# mainboard_r15_eurobot2014_r1.net
KiCad netlist of a schematic drawn in EAGLE
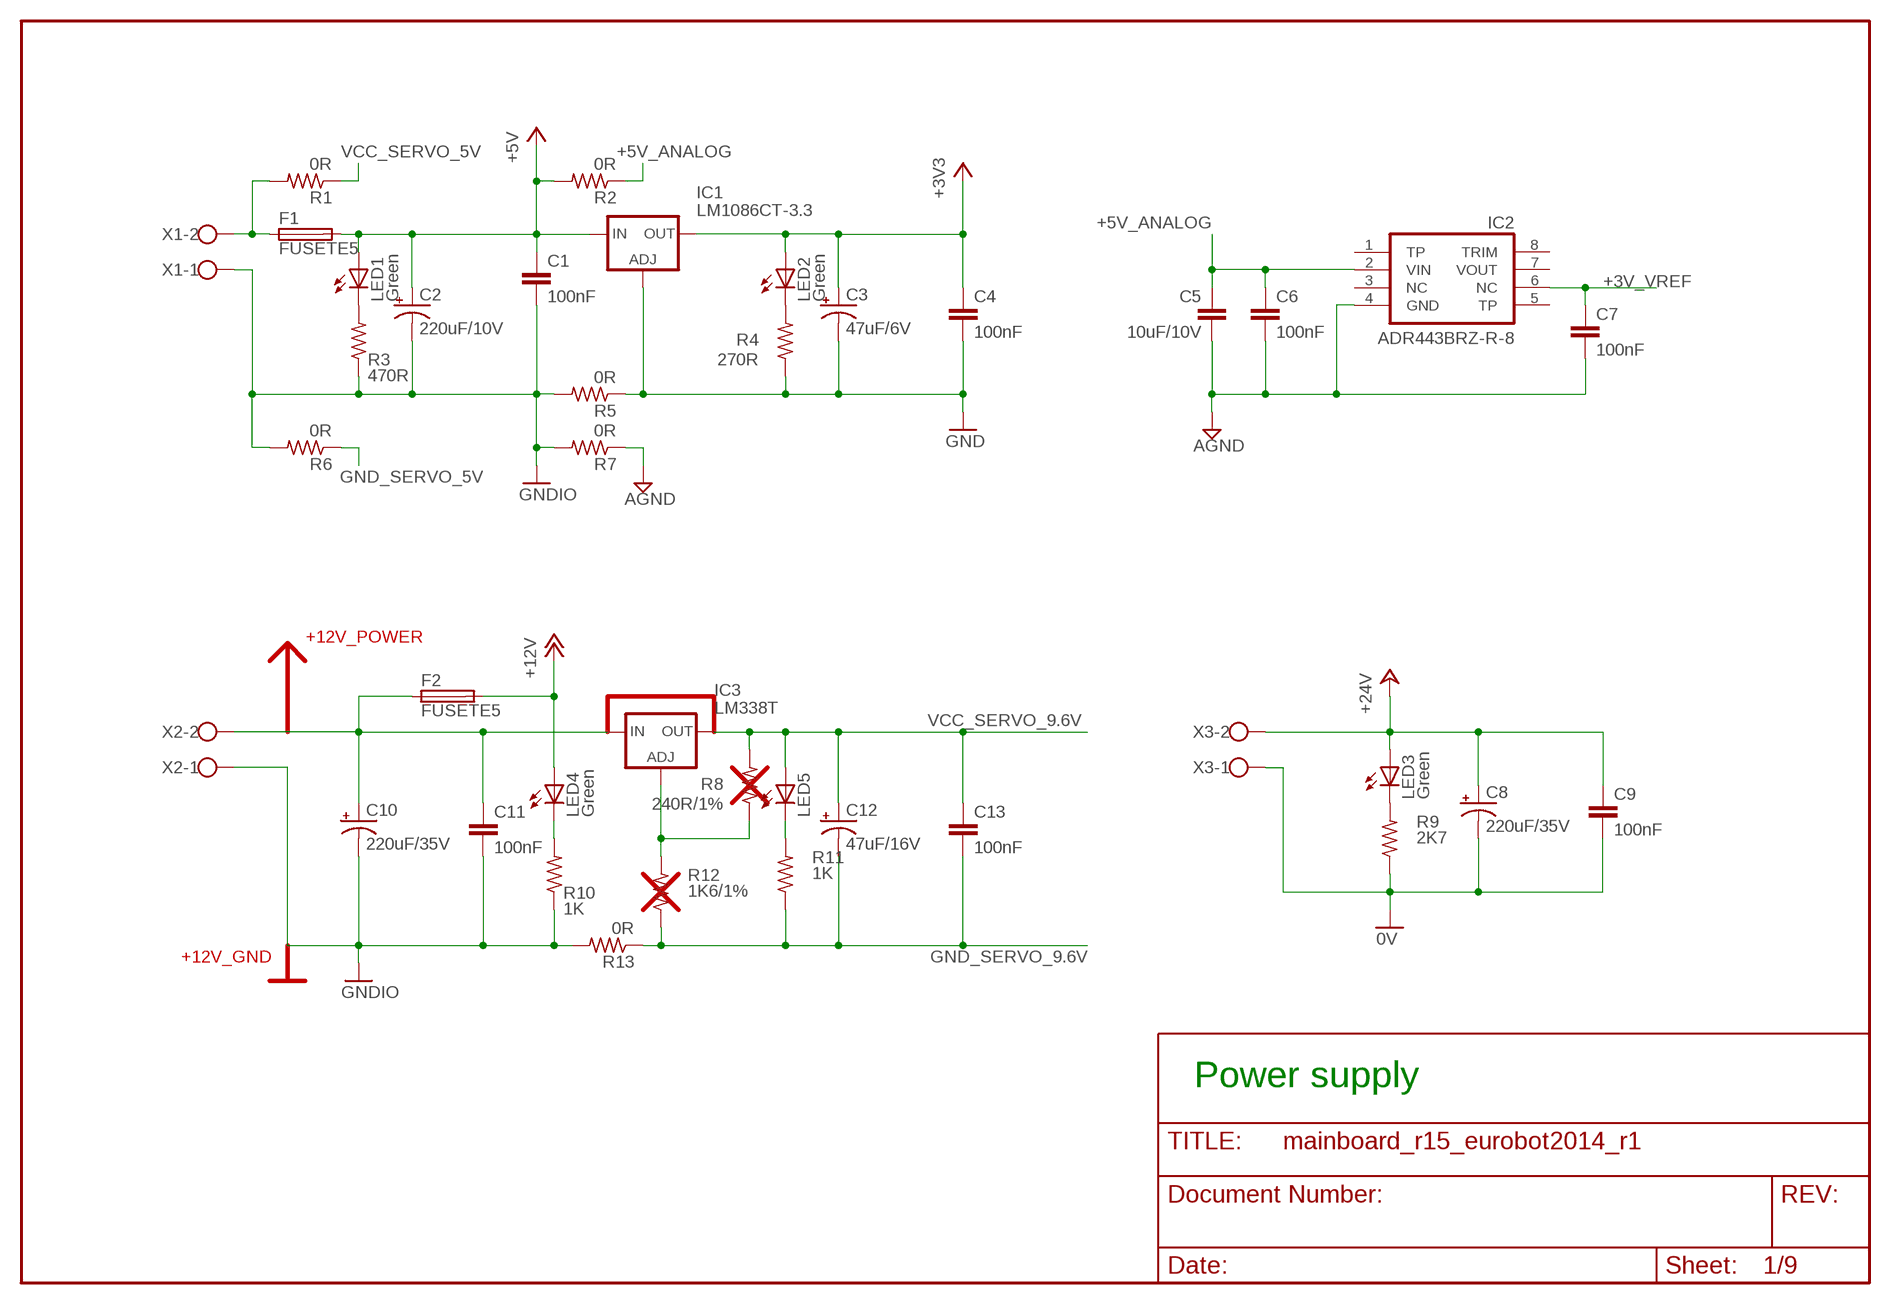
[diagram p0: schematic, sheet 1]
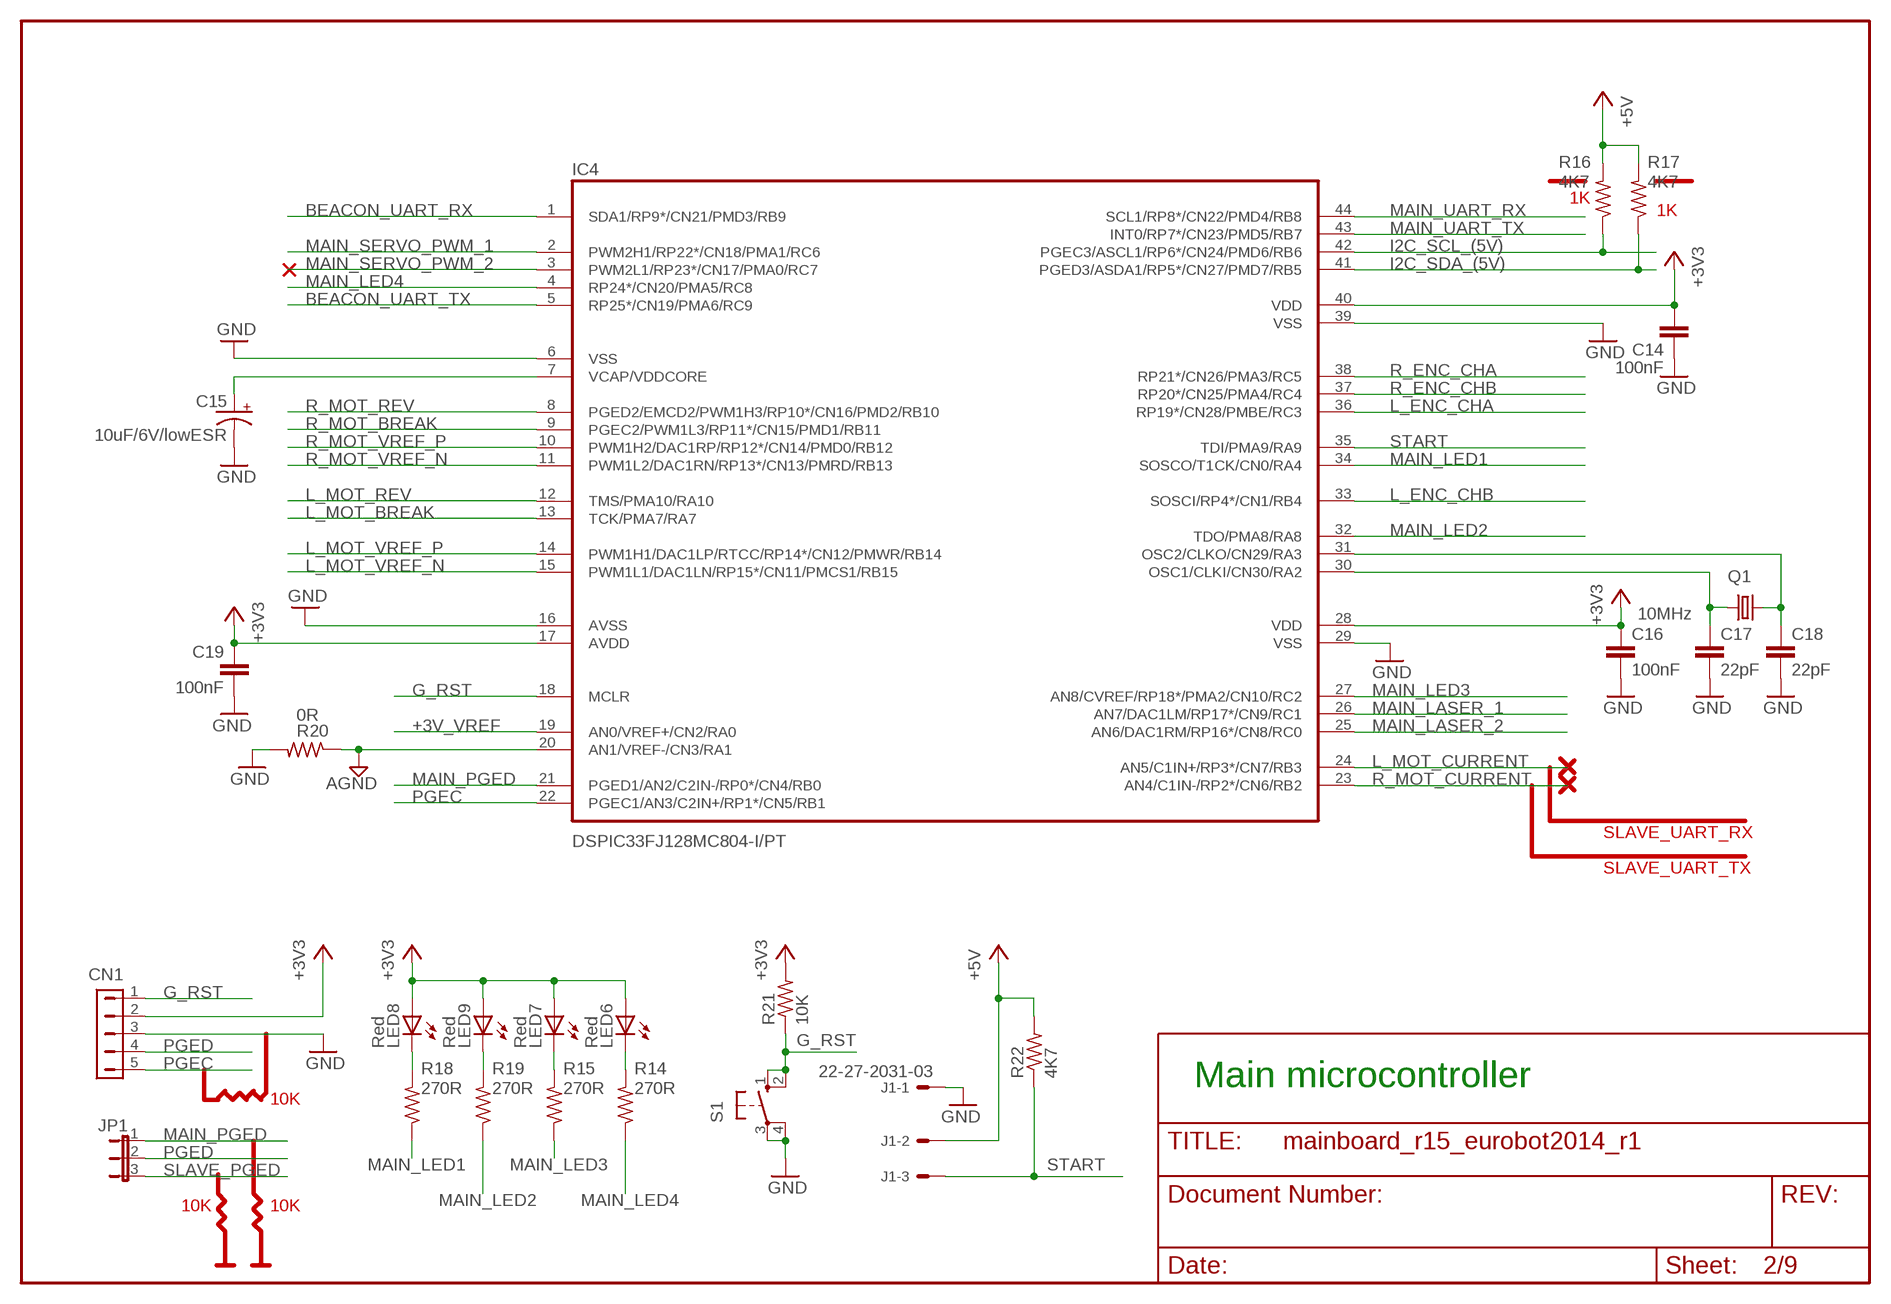
[diagram p1: schematic, sheet 2]
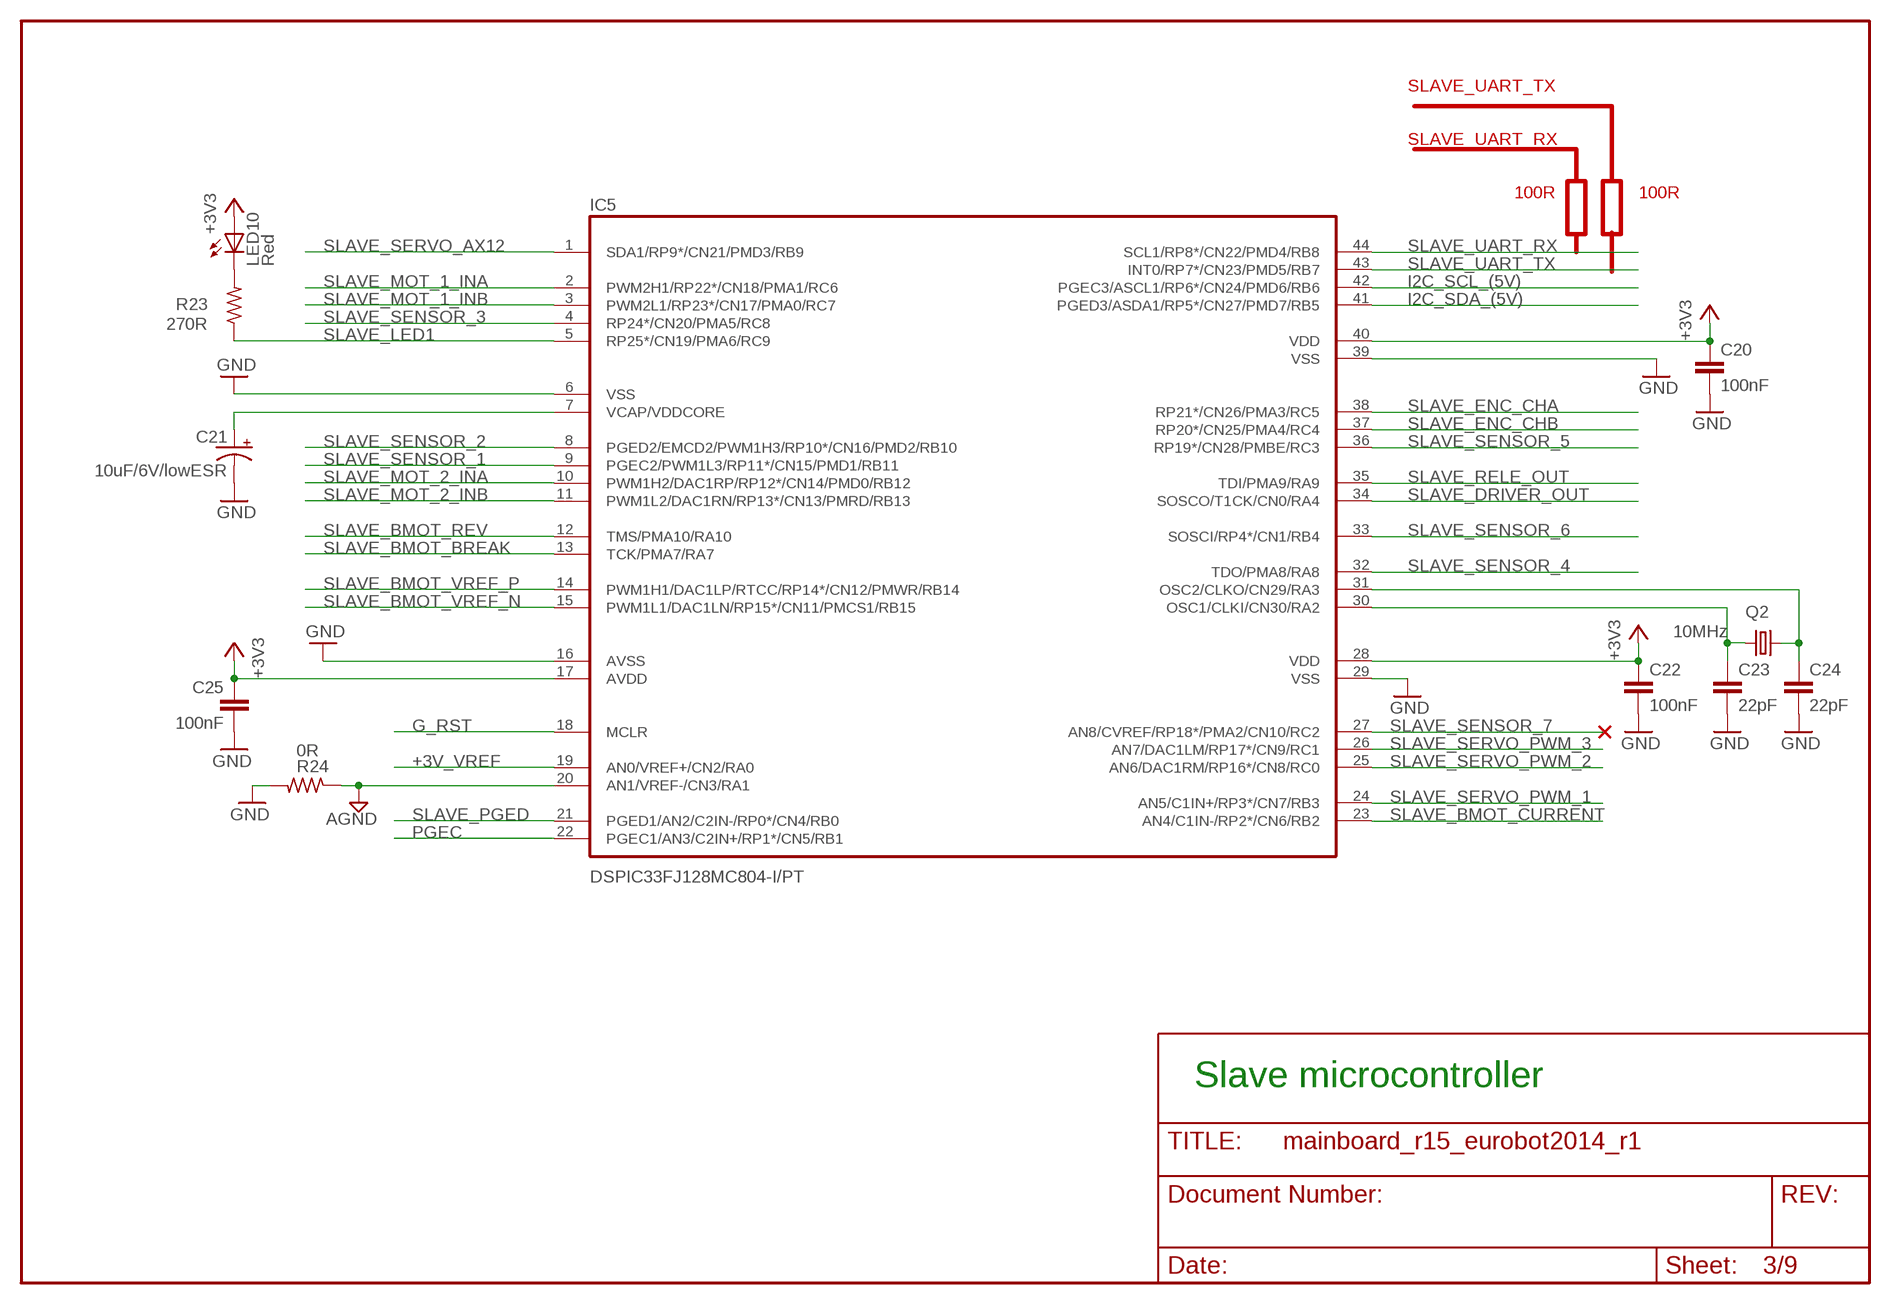
[diagram p2: schematic, sheet 3]
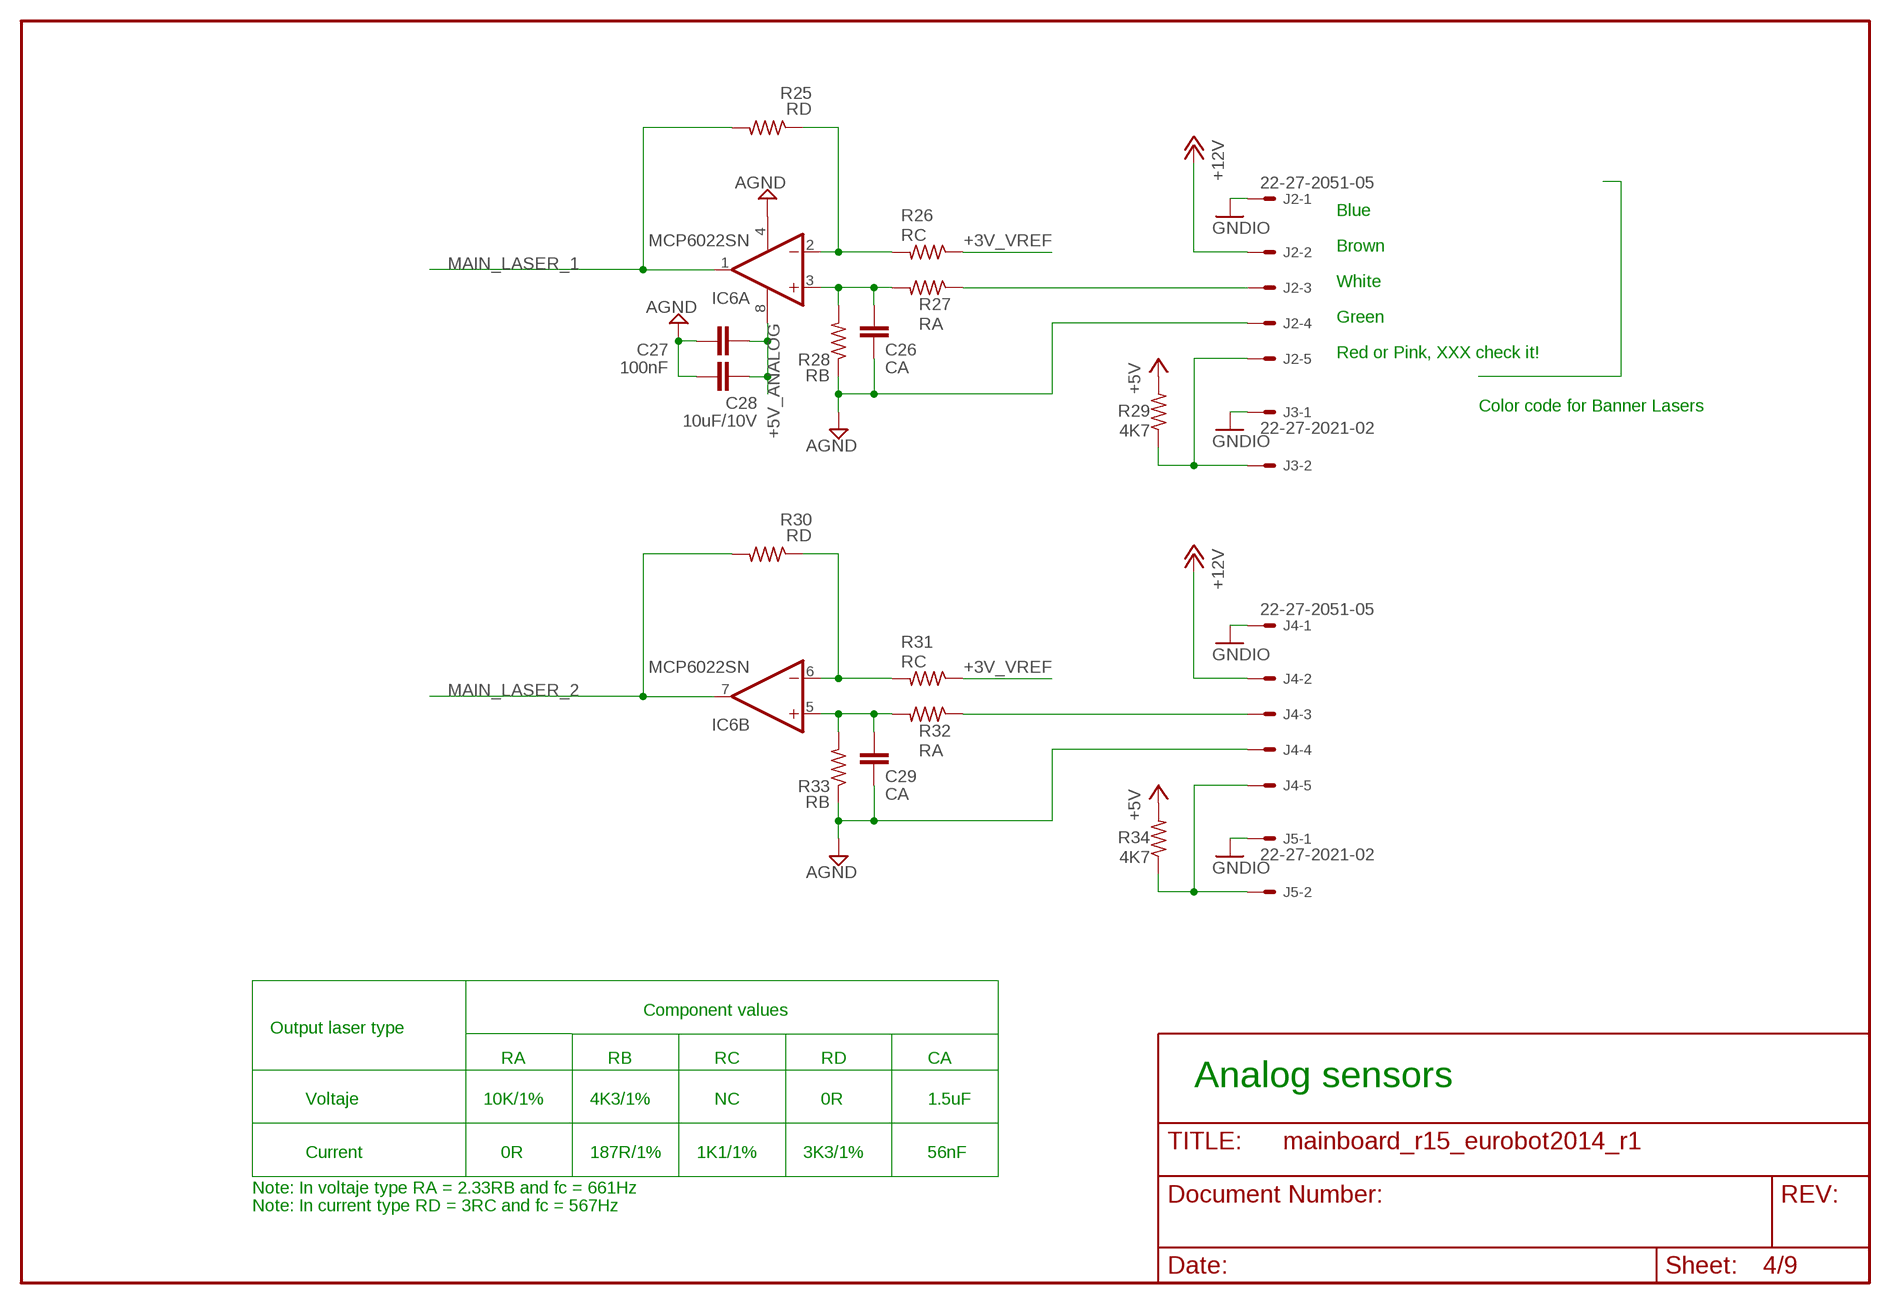
[diagram p3: schematic, sheet 4]
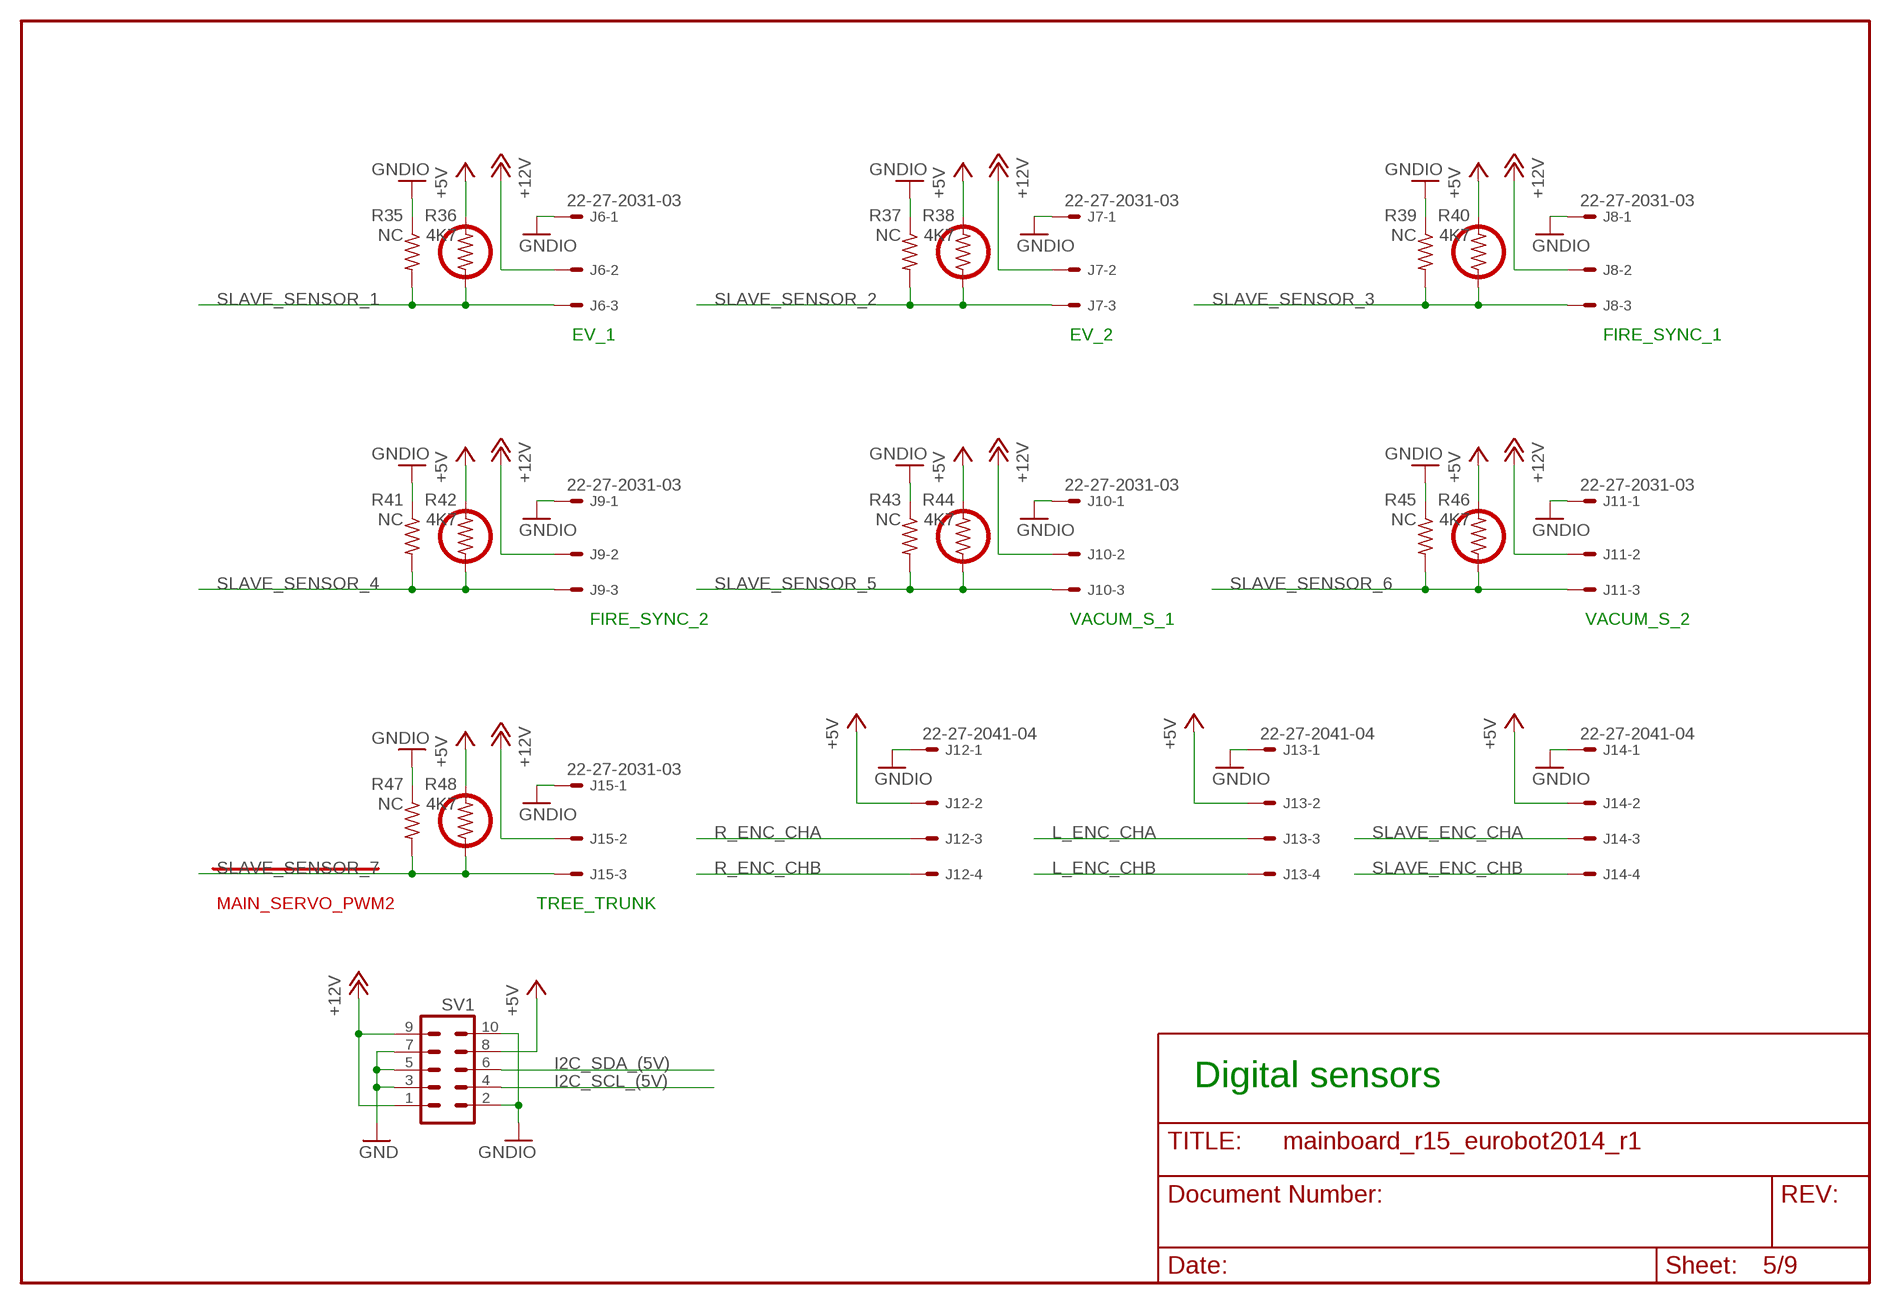
[diagram p4: schematic, sheet 5]
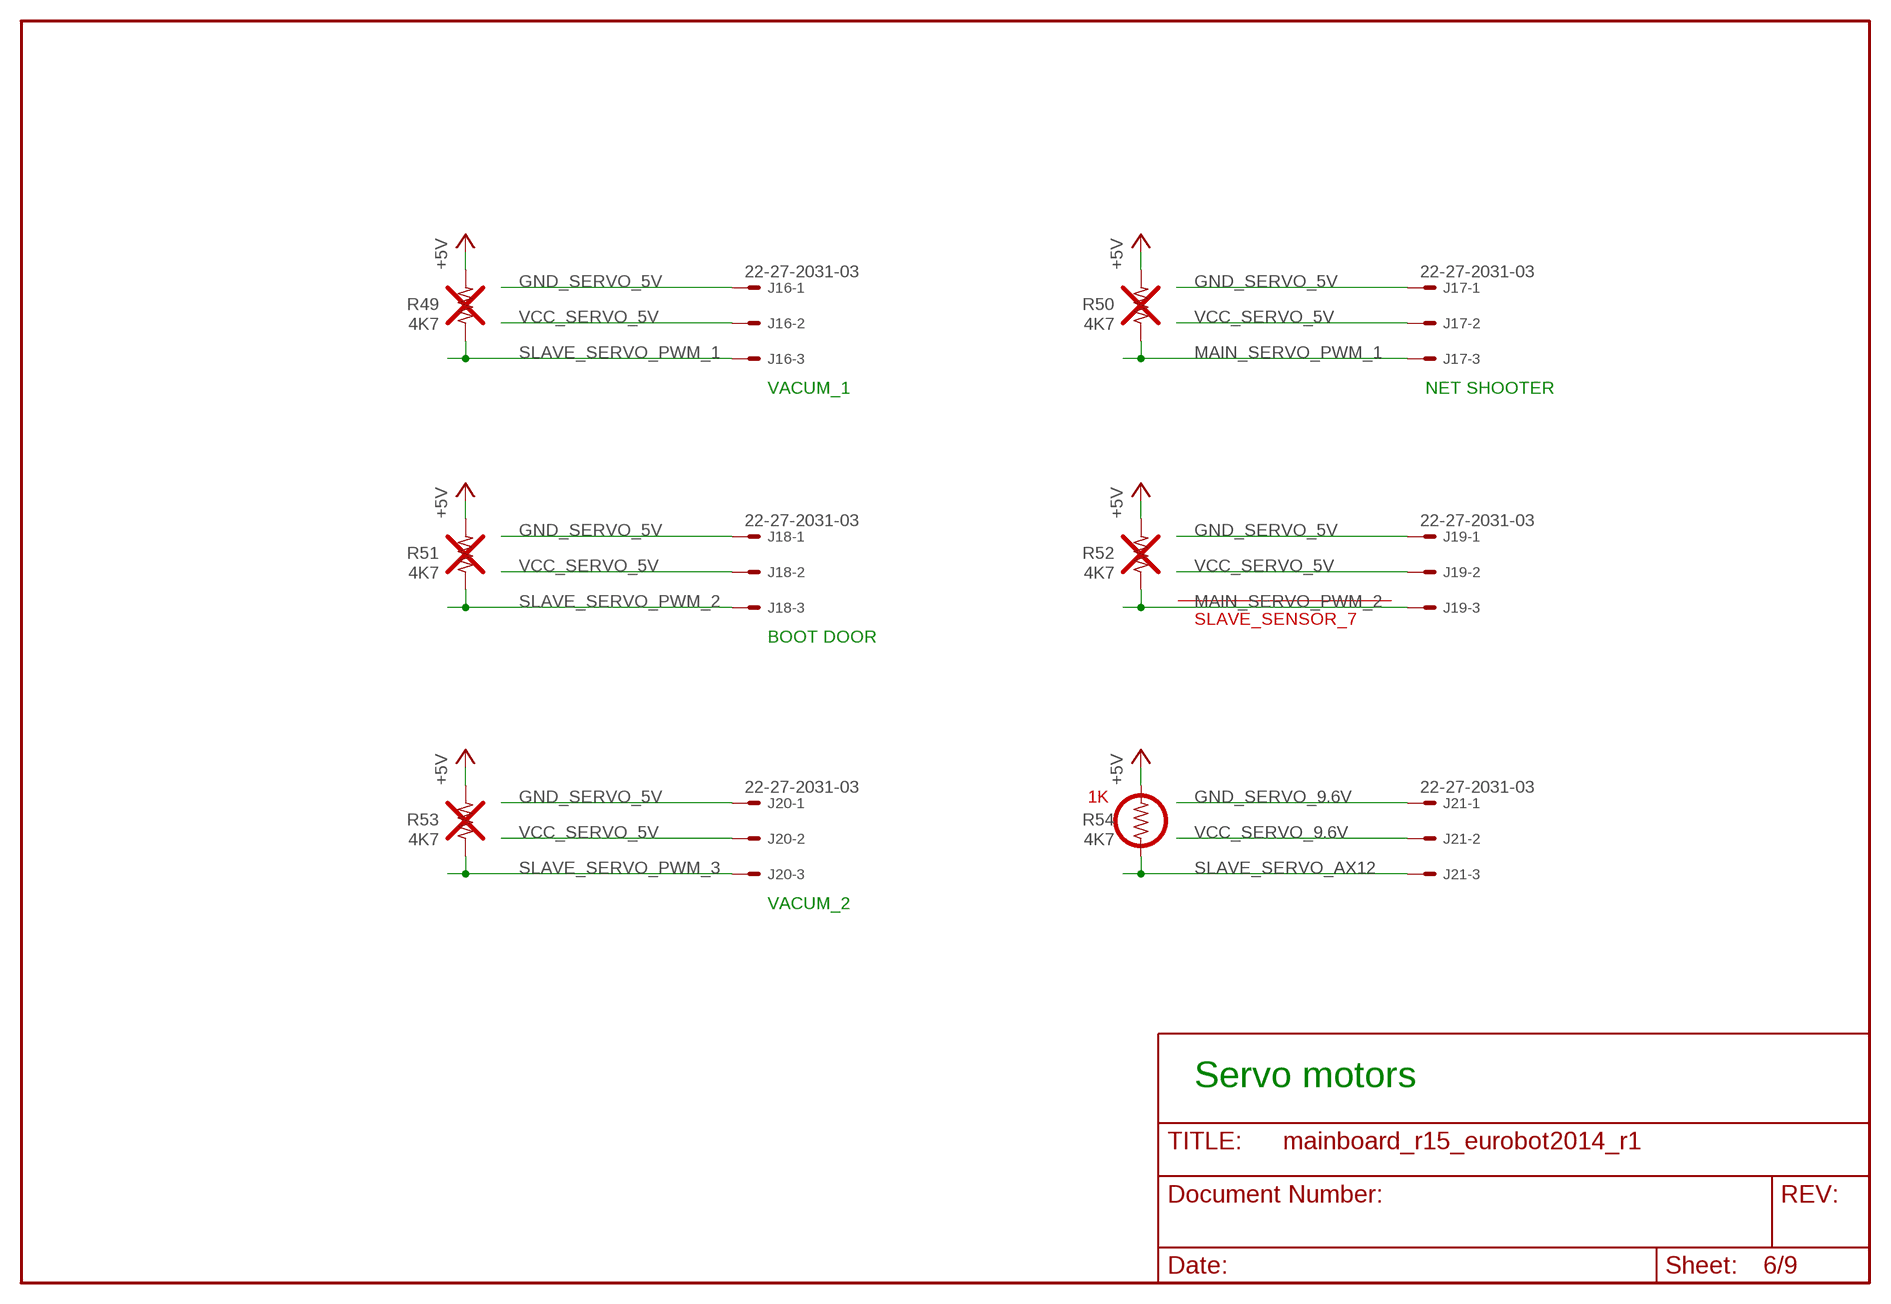
[diagram p5: schematic, sheet 6]
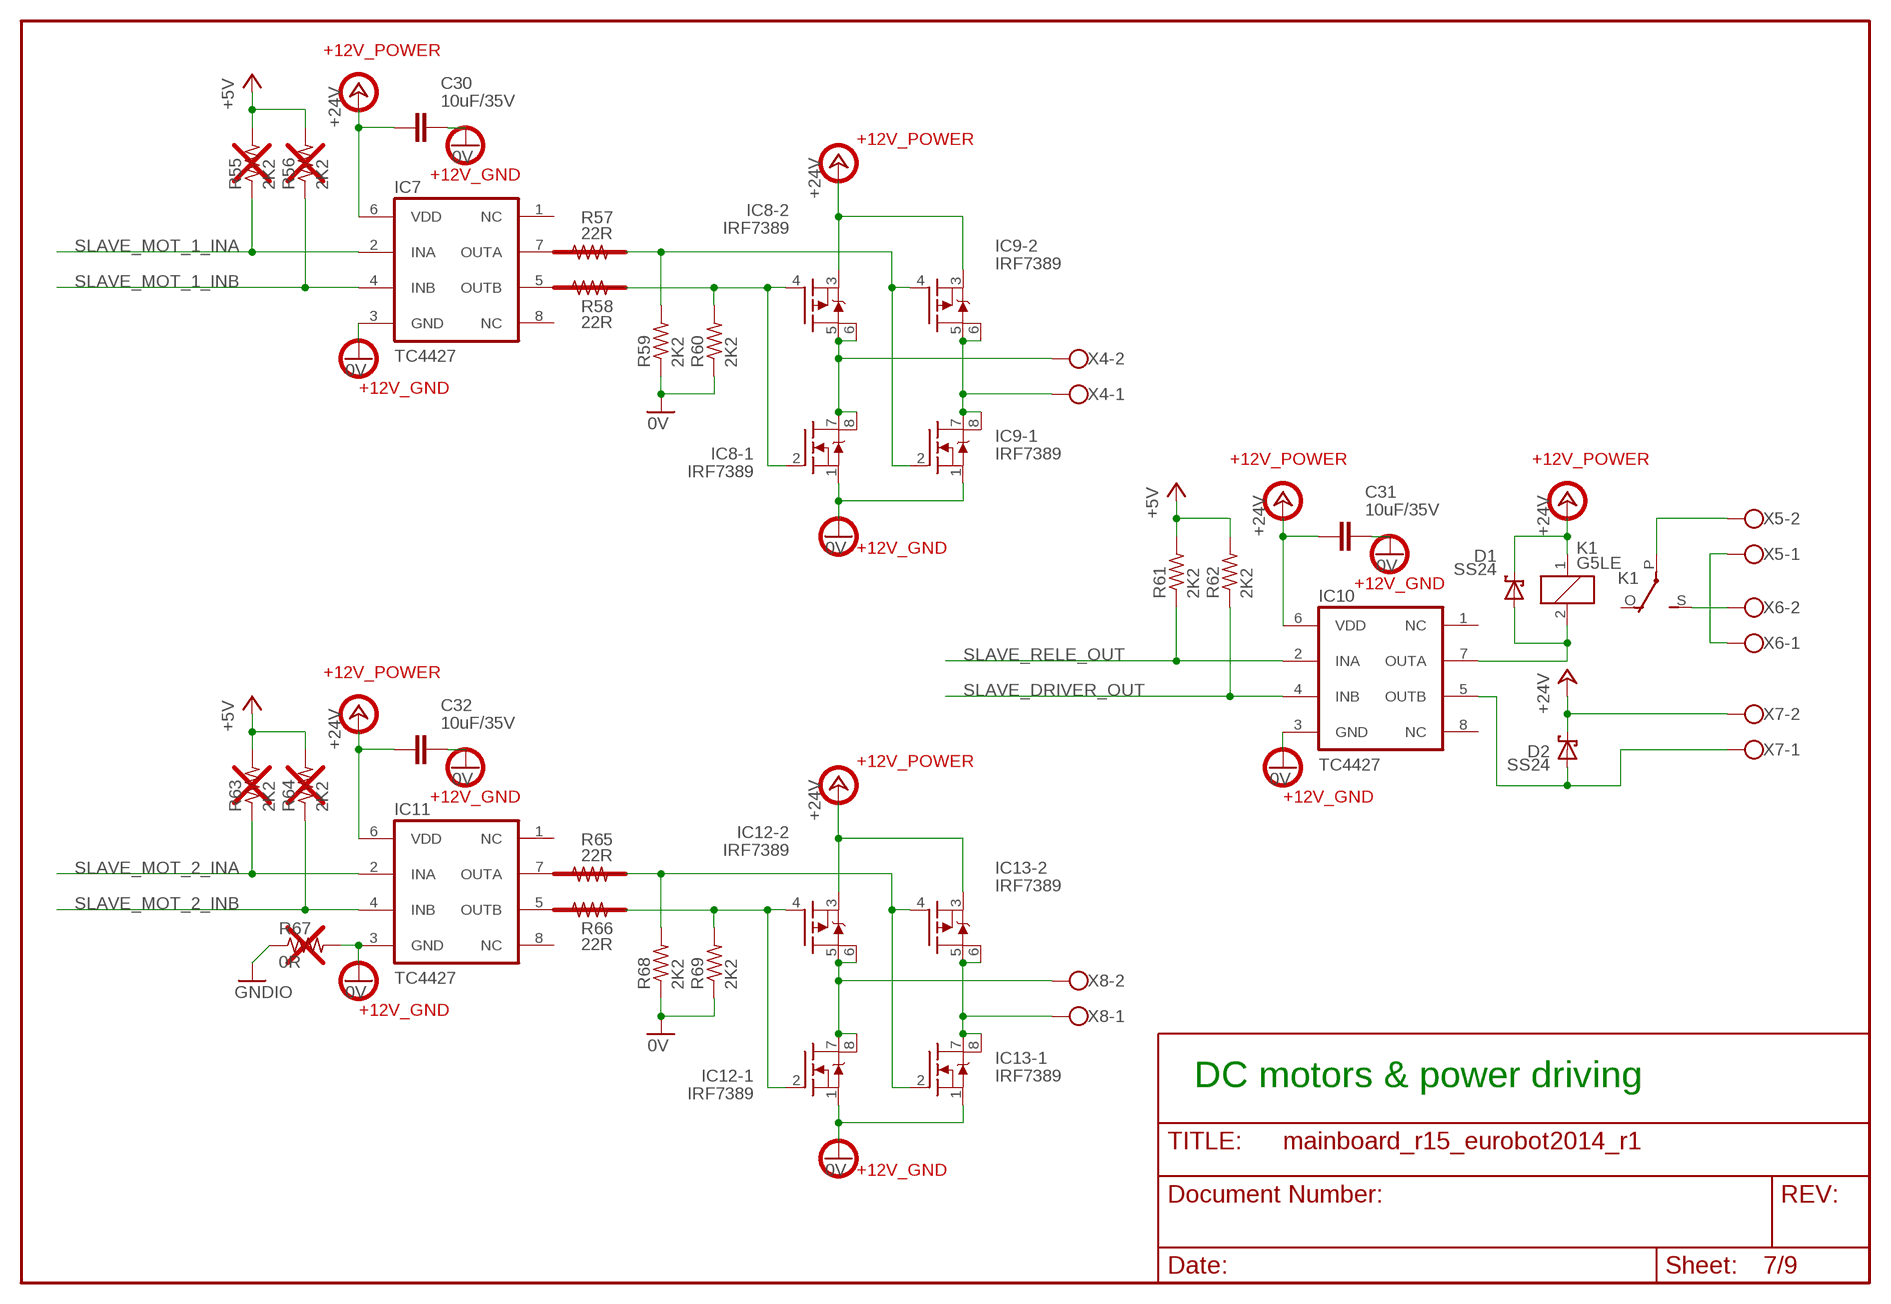
[diagram p6: schematic, sheet 7]
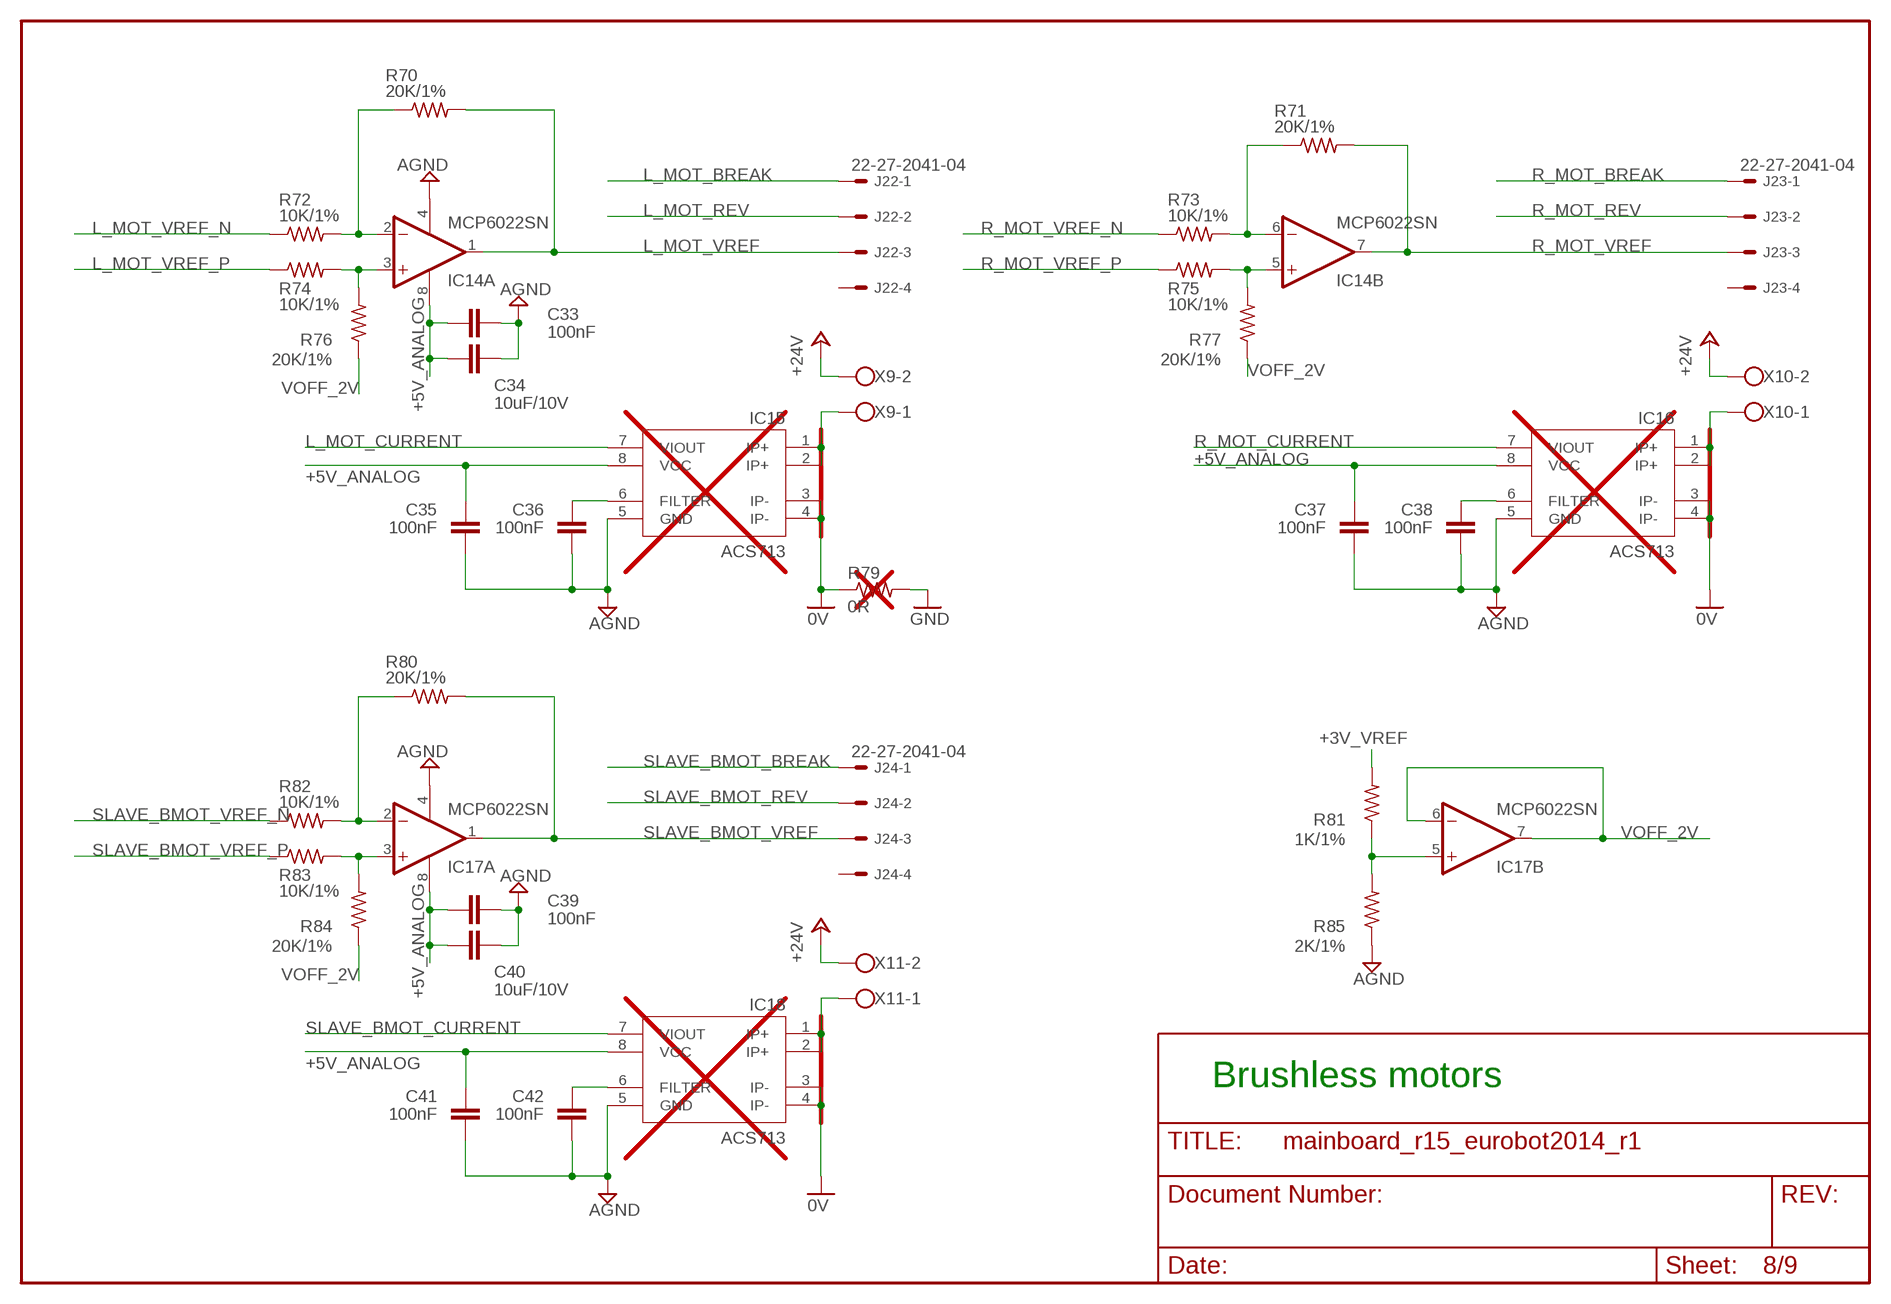
[diagram p7: schematic, sheet 8]
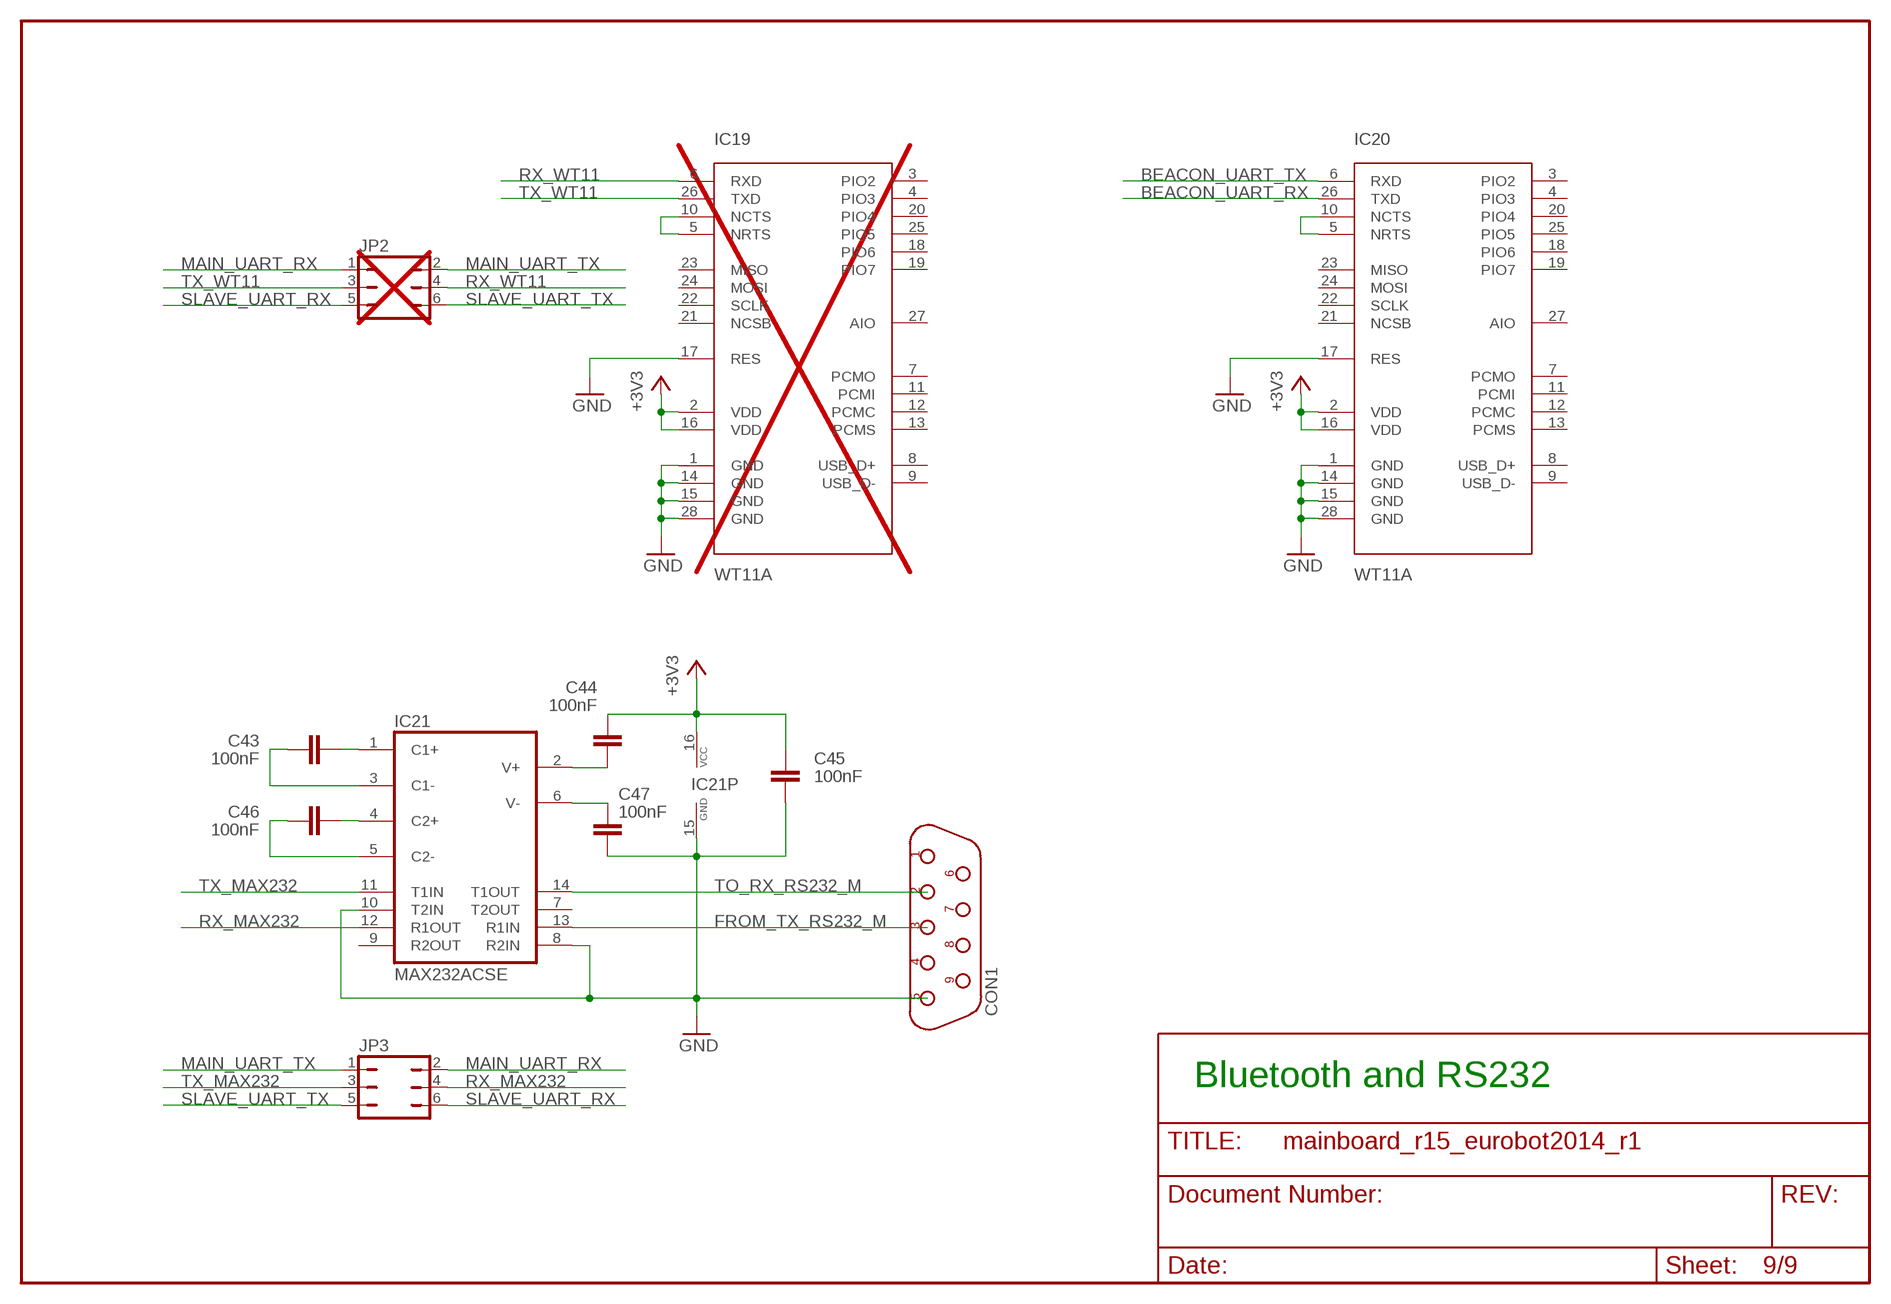
[diagram p8: schematic, sheet 9]

(export (version "E")
  (design (tool "Eeschema 10.0.6"))
  (components
    (comp (ref "C20")
      (value "100nF")
      (footprint "eagle-import:C0603")
      (libsource (lib "eagle-import") (part "C-EUC0603"))
    )
    (comp (ref "C21")
      (value "10uF/6V/lowESR")
      (footprint "eagle-import:SMC_A")
      (libsource (lib "eagle-import") (part "CPOL-USSMCA"))
    )
    (comp (ref "C22")
      (value "100nF")
      (footprint "eagle-import:C0603")
      (libsource (lib "eagle-import") (part "C-EUC0603"))
    )
    (comp (ref "C23")
      (value "22pF")
      (footprint "eagle-import:C0805")
      (libsource (lib "eagle-import") (part "C-EUC0805"))
    )
    (comp (ref "C24")
      (value "22pF")
      (footprint "eagle-import:C0805")
      (libsource (lib "eagle-import") (part "C-EUC0805"))
    )
    (comp (ref "C25")
      (value "100nF")
      (footprint "eagle-import:C0603")
      (libsource (lib "eagle-import") (part "C-EUC0603"))
    )
    (comp (ref "IC5")
      (value "DSPIC33FJ128MC804-I/PT")
      (footprint "eagle-import:TQFP44")
      (libsource (lib "eagle-import") (part "DSPIC33FJXXMC804SMD"))
    )
    (comp (ref "LED10")
      (value "Red")
      (footprint "eagle-import:CHIP-LED0805")
      (libsource (lib "eagle-import") (part "LEDCHIP-LED0805"))
    )
    (comp (ref "Q2")
      (value "10MHz")
      (footprint "eagle-import:HC49UP")
      (libsource (lib "eagle-import") (part "CRYSTALHC49UP"))
    )
    (comp (ref "R23")
      (value "270R")
      (footprint "eagle-import:R0805")
      (libsource (lib "eagle-import") (part "R-US_R0805"))
    )
    (comp (ref "R24")
      (value "0R")
      (footprint "eagle-import:R0805")
      (libsource (lib "eagle-import") (part "R-US_R0805"))
    )
    (comp (ref "C30")
      (value "10uF/35V")
      (footprint "eagle-import:C1206")
      (libsource (lib "eagle-import") (part "C-EUC1206"))
    )
    (comp (ref "C31")
      (value "10uF/35V")
      (footprint "eagle-import:C1206")
      (libsource (lib "eagle-import") (part "C-EUC1206"))
    )
    (comp (ref "C32")
      (value "10uF/35V")
      (footprint "eagle-import:C1206")
      (libsource (lib "eagle-import") (part "C-EUC1206"))
    )
    (comp (ref "D1")
      (value "SS24")
      (footprint "eagle-import:DIOM5436X265N")
      (libsource (lib "eagle-import") (part "SCHOTTKY_SMB"))
    )
    (comp (ref "D2")
      (value "SS24")
      (footprint "eagle-import:DIOM5436X265N")
      (libsource (lib "eagle-import") (part "SCHOTTKY_SMB"))
    )
    (comp (ref "IC7")
      (value "TC4427")
      (footprint "eagle-import:SO08")
      (libsource (lib "eagle-import") (part "TC4427OA"))
    )
    (comp (ref "IC8")
      (value "IRF7389")
      (footprint "eagle-import:SO08")
      (libsource (lib "eagle-import") (part "IRF7389"))
    )
    (comp (ref "IC9")
      (value "IRF7389")
      (footprint "eagle-import:SO08")
      (libsource (lib "eagle-import") (part "IRF7389"))
    )
    (comp (ref "IC10")
      (value "TC4427")
      (footprint "eagle-import:SO08")
      (libsource (lib "eagle-import") (part "TC4427OA"))
    )
    (comp (ref "IC11")
      (value "TC4427")
      (footprint "eagle-import:SO08")
      (libsource (lib "eagle-import") (part "TC4427OA"))
    )
    (comp (ref "IC12")
      (value "IRF7389")
      (footprint "eagle-import:SO08")
      (libsource (lib "eagle-import") (part "IRF7389"))
    )
    (comp (ref "IC13")
      (value "IRF7389")
      (footprint "eagle-import:SO08")
      (libsource (lib "eagle-import") (part "IRF7389"))
    )
    (comp (ref "K1")
      (value "G5LE")
      (footprint "eagle-import:G5LE")
      (libsource (lib "eagle-import") (part "G5LE"))
    )
    (comp (ref "R55")
      (value "2K2")
      (footprint "eagle-import:R0805")
      (libsource (lib "eagle-import") (part "R-US_R0805"))
    )
    (comp (ref "R56")
      (value "2K2")
      (footprint "eagle-import:R0805")
      (libsource (lib "eagle-import") (part "R-US_R0805"))
    )
    (comp (ref "R57")
      (value "22R")
      (footprint "eagle-import:R0805")
      (libsource (lib "eagle-import") (part "R-US_R0805"))
    )
    (comp (ref "R58")
      (value "22R")
      (footprint "eagle-import:R0805")
      (libsource (lib "eagle-import") (part "R-US_R0805"))
    )
    (comp (ref "R59")
      (value "2K2")
      (footprint "eagle-import:R0805")
      (libsource (lib "eagle-import") (part "R-US_R0805"))
    )
    (comp (ref "R60")
      (value "2K2")
      (footprint "eagle-import:R0805")
      (libsource (lib "eagle-import") (part "R-US_R0805"))
    )
    (comp (ref "R61")
      (value "2K2")
      (footprint "eagle-import:R0805")
      (libsource (lib "eagle-import") (part "R-US_R0805"))
    )
    (comp (ref "R62")
      (value "2K2")
      (footprint "eagle-import:R0805")
      (libsource (lib "eagle-import") (part "R-US_R0805"))
    )
    (comp (ref "R63")
      (value "2K2")
      (footprint "eagle-import:R0805")
      (libsource (lib "eagle-import") (part "R-US_R0805"))
    )
    (comp (ref "R64")
      (value "2K2")
      (footprint "eagle-import:R0805")
      (libsource (lib "eagle-import") (part "R-US_R0805"))
    )
    (comp (ref "R65")
      (value "22R")
      (footprint "eagle-import:R0805")
      (libsource (lib "eagle-import") (part "R-US_R0805"))
    )
    (comp (ref "R66")
      (value "22R")
      (footprint "eagle-import:R0805")
      (libsource (lib "eagle-import") (part "R-US_R0805"))
    )
    (comp (ref "R67")
      (value "0R")
      (footprint "eagle-import:R0805")
      (libsource (lib "eagle-import") (part "R-US_R0805"))
    )
    (comp (ref "R68")
      (value "2K2")
      (footprint "eagle-import:R0805")
      (libsource (lib "eagle-import") (part "R-US_R0805"))
    )
    (comp (ref "R69")
      (value "2K2")
      (footprint "eagle-import:R0805")
      (libsource (lib "eagle-import") (part "R-US_R0805"))
    )
    (comp (ref "X4")
      (value "W237-02P")
      (footprint "eagle-import:W237-132")
      (libsource (lib "eagle-import") (part "W237-02P"))
    )
    (comp (ref "X5")
      (value "W237-02P")
      (footprint "eagle-import:W237-132")
      (libsource (lib "eagle-import") (part "W237-02P"))
    )
    (comp (ref "X6")
      (value "W237-02P")
      (footprint "eagle-import:W237-132")
      (libsource (lib "eagle-import") (part "W237-02P"))
    )
    (comp (ref "X7")
      (value "W237-02P")
      (footprint "eagle-import:W237-132")
      (libsource (lib "eagle-import") (part "W237-02P"))
    )
    (comp (ref "X8")
      (value "W237-02P")
      (footprint "eagle-import:W237-132")
      (libsource (lib "eagle-import") (part "W237-02P"))
    )
    (comp (ref "J16")
      (value "22-27-2031-03")
      (footprint "eagle-import:6410-03")
      (libsource (lib "eagle-import") (part "22-?-0327-2031"))
    )
    (comp (ref "J17")
      (value "22-27-2031-03")
      (footprint "eagle-import:6410-03")
      (libsource (lib "eagle-import") (part "22-?-0327-2031"))
    )
    (comp (ref "J18")
      (value "22-27-2031-03")
      (footprint "eagle-import:6410-03")
      (libsource (lib "eagle-import") (part "22-?-0327-2031"))
    )
    (comp (ref "J19")
      (value "22-27-2031-03")
      (footprint "eagle-import:6410-03")
      (libsource (lib "eagle-import") (part "22-?-0327-2031"))
    )
    (comp (ref "J20")
      (value "22-27-2031-03")
      (footprint "eagle-import:6410-03")
      (libsource (lib "eagle-import") (part "22-?-0327-2031"))
    )
    (comp (ref "J21")
      (value "22-27-2031-03")
      (footprint "eagle-import:6410-03")
      (libsource (lib "eagle-import") (part "22-?-0327-2031"))
    )
    (comp (ref "R49")
      (value "4K7")
      (footprint "eagle-import:R0805")
      (libsource (lib "eagle-import") (part "R-US_R0805"))
    )
    (comp (ref "R50")
      (value "4K7")
      (footprint "eagle-import:R0805")
      (libsource (lib "eagle-import") (part "R-US_R0805"))
    )
    (comp (ref "R51")
      (value "4K7")
      (footprint "eagle-import:R0805")
      (libsource (lib "eagle-import") (part "R-US_R0805"))
    )
    (comp (ref "R52")
      (value "4K7")
      (footprint "eagle-import:R0805")
      (libsource (lib "eagle-import") (part "R-US_R0805"))
    )
    (comp (ref "R53")
      (value "4K7")
      (footprint "eagle-import:R0805")
      (libsource (lib "eagle-import") (part "R-US_R0805"))
    )
    (comp (ref "R54")
      (value "4K7")
      (footprint "eagle-import:R0805")
      (libsource (lib "eagle-import") (part "R-US_R0805"))
    )
    (comp (ref "C33")
      (value "100nF")
      (footprint "eagle-import:C0805")
      (libsource (lib "eagle-import") (part "C-EUC0805"))
    )
    (comp (ref "C34")
      (value "10uF/10V")
      (footprint "eagle-import:C1206")
      (libsource (lib "eagle-import") (part "C-EUC1206"))
    )
    (comp (ref "C35")
      (value "100nF")
      (footprint "eagle-import:C0805")
      (libsource (lib "eagle-import") (part "C-EUC0805"))
    )
    (comp (ref "C36")
      (value "100nF")
      (footprint "eagle-import:C0805")
      (libsource (lib "eagle-import") (part "C-EUC0805"))
    )
    (comp (ref "C37")
      (value "100nF")
      (footprint "eagle-import:C0805")
      (libsource (lib "eagle-import") (part "C-EUC0805"))
    )
    (comp (ref "C38")
      (value "100nF")
      (footprint "eagle-import:C0805")
      (libsource (lib "eagle-import") (part "C-EUC0805"))
    )
    (comp (ref "C39")
      (value "100nF")
      (footprint "eagle-import:C0805")
      (libsource (lib "eagle-import") (part "C-EUC0805"))
    )
    (comp (ref "C40")
      (value "10uF/10V")
      (footprint "eagle-import:C1206")
      (libsource (lib "eagle-import") (part "C-EUC1206"))
    )
    (comp (ref "C41")
      (value "100nF")
      (footprint "eagle-import:C0805")
      (libsource (lib "eagle-import") (part "C-EUC0805"))
    )
    (comp (ref "C42")
      (value "100nF")
      (footprint "eagle-import:C0805")
      (libsource (lib "eagle-import") (part "C-EUC0805"))
    )
    (comp (ref "IC14")
      (value "MCP6022SN")
      (footprint "eagle-import:SO08")
      (libsource (lib "eagle-import") (part "OPA2U344"))
    )
    (comp (ref "IC15")
      (value "ACS713")
      (footprint "eagle-import:SO08")
      (libsource (lib "eagle-import") (part "ADS713"))
    )
    (comp (ref "IC16")
      (value "ACS713")
      (footprint "eagle-import:SO08")
      (libsource (lib "eagle-import") (part "ADS713"))
    )
    (comp (ref "IC17")
      (value "MCP6022SN")
      (footprint "eagle-import:SO08")
      (libsource (lib "eagle-import") (part "OPA2U344"))
    )
    (comp (ref "IC18")
      (value "ACS713")
      (footprint "eagle-import:SO08")
      (libsource (lib "eagle-import") (part "ADS713"))
    )
    (comp (ref "J22")
      (value "22-27-2041-04")
      (footprint "eagle-import:6410-04")
      (libsource (lib "eagle-import") (part "22-?-0427-2041"))
    )
    (comp (ref "J23")
      (value "22-27-2041-04")
      (footprint "eagle-import:6410-04")
      (libsource (lib "eagle-import") (part "22-?-0427-2041"))
    )
    (comp (ref "J24")
      (value "22-27-2041-04")
      (footprint "eagle-import:6410-04")
      (libsource (lib "eagle-import") (part "22-?-0427-2041"))
    )
    (comp (ref "R70")
      (value "20K/1%")
      (footprint "eagle-import:R0805")
      (libsource (lib "eagle-import") (part "R-US_R0805"))
    )
    (comp (ref "R71")
      (value "20K/1%")
      (footprint "eagle-import:R0805")
      (libsource (lib "eagle-import") (part "R-US_R0805"))
    )
    (comp (ref "R72")
      (value "10K/1%")
      (footprint "eagle-import:R0805")
      (libsource (lib "eagle-import") (part "R-US_R0805"))
    )
    (comp (ref "R73")
      (value "10K/1%")
      (footprint "eagle-import:R0805")
      (libsource (lib "eagle-import") (part "R-US_R0805"))
    )
    (comp (ref "R74")
      (value "10K/1%")
      (footprint "eagle-import:R0805")
      (libsource (lib "eagle-import") (part "R-US_R0805"))
    )
    (comp (ref "R75")
      (value "10K/1%")
      (footprint "eagle-import:R0805")
      (libsource (lib "eagle-import") (part "R-US_R0805"))
    )
    (comp (ref "R76")
      (value "20K/1%")
      (footprint "eagle-import:R0805")
      (libsource (lib "eagle-import") (part "R-US_R0805"))
    )
    (comp (ref "R77")
      (value "20K/1%")
      (footprint "eagle-import:R0805")
      (libsource (lib "eagle-import") (part "R-US_R0805"))
    )
    (comp (ref "R79")
      (value "0R")
      (footprint "eagle-import:R0805")
      (libsource (lib "eagle-import") (part "R-US_R0805"))
    )
    (comp (ref "R80")
      (value "20K/1%")
      (footprint "eagle-import:R0805")
      (libsource (lib "eagle-import") (part "R-US_R0805"))
    )
    (comp (ref "R81")
      (value "1K/1%")
      (footprint "eagle-import:R0805")
      (libsource (lib "eagle-import") (part "R-US_R0805"))
    )
    (comp (ref "R82")
      (value "10K/1%")
      (footprint "eagle-import:R0805")
      (libsource (lib "eagle-import") (part "R-US_R0805"))
    )
    (comp (ref "R83")
      (value "10K/1%")
      (footprint "eagle-import:R0805")
      (libsource (lib "eagle-import") (part "R-US_R0805"))
    )
    (comp (ref "R84")
      (value "20K/1%")
      (footprint "eagle-import:R0805")
      (libsource (lib "eagle-import") (part "R-US_R0805"))
    )
    (comp (ref "R85")
      (value "2K/1%")
      (footprint "eagle-import:R0805")
      (libsource (lib "eagle-import") (part "R-US_R0805"))
    )
    (comp (ref "X9")
      (value "W237-02P")
      (footprint "eagle-import:W237-132")
      (libsource (lib "eagle-import") (part "W237-02P"))
    )
    (comp (ref "X10")
      (value "W237-02P")
      (footprint "eagle-import:W237-132")
      (libsource (lib "eagle-import") (part "W237-02P"))
    )
    (comp (ref "X11")
      (value "W237-02P")
      (footprint "eagle-import:W237-132")
      (libsource (lib "eagle-import") (part "W237-02P"))
    )
    (comp (ref "C43")
      (value "100nF")
      (footprint "eagle-import:C0603")
      (libsource (lib "eagle-import") (part "C-EUC0603"))
    )
    (comp (ref "C44")
      (value "100nF")
      (footprint "eagle-import:C0603")
      (libsource (lib "eagle-import") (part "C-EUC0603"))
    )
    (comp (ref "C45")
      (value "100nF")
      (footprint "eagle-import:C0603")
      (libsource (lib "eagle-import") (part "C-EUC0603"))
    )
    (comp (ref "C46")
      (value "100nF")
      (footprint "eagle-import:C0603")
      (libsource (lib "eagle-import") (part "C-EUC0603"))
    )
    (comp (ref "C47")
      (value "100nF")
      (footprint "eagle-import:C0603")
      (libsource (lib "eagle-import") (part "C-EUC0603"))
    )
    (comp (ref "CON1")
      (value "DB9F/90")
      (footprint "eagle-import:D-09F_90")
      (libsource (lib "eagle-import") (part "DB9F/90"))
    )
    (comp (ref "IC19")
      (value "WT11A")
      (footprint "eagle-import:WT11")
      (libsource (lib "eagle-import") (part "WT11A"))
    )
    (comp (ref "IC20")
      (value "WT11A")
      (footprint "eagle-import:WT11")
      (libsource (lib "eagle-import") (part "WT11A"))
    )
    (comp (ref "IC21")
      (value "MAX232ACSE")
      (footprint "eagle-import:SO16")
      (libsource (lib "eagle-import") (part "MAX232SEAC"))
    )
    (comp (ref "JP2")
      (value "JP3Q")
      (footprint "eagle-import:JP3Q")
      (libsource (lib "eagle-import") (part "JP3Q"))
    )
    (comp (ref "JP3")
      (value "JP3Q")
      (footprint "eagle-import:JP3Q")
      (libsource (lib "eagle-import") (part "JP3Q"))
    )
    (comp (ref "C26")
      (value "CA")
      (footprint "eagle-import:C0805")
      (libsource (lib "eagle-import") (part "C-EUC0805"))
    )
    (comp (ref "C27")
      (value "100nF")
      (footprint "eagle-import:C0805")
      (libsource (lib "eagle-import") (part "C-EUC0805"))
    )
    (comp (ref "C28")
      (value "10uF/10V")
      (footprint "eagle-import:C1206")
      (libsource (lib "eagle-import") (part "C-EUC1206"))
    )
    (comp (ref "C29")
      (value "CA")
      (footprint "eagle-import:C0805")
      (libsource (lib "eagle-import") (part "C-EUC0805"))
    )
    (comp (ref "IC6")
      (value "MCP6022SN")
      (footprint "eagle-import:SO08")
      (libsource (lib "eagle-import") (part "OPA2U344"))
    )
    (comp (ref "J2")
      (value "22-27-2051-05")
      (footprint "eagle-import:6410-05")
      (libsource (lib "eagle-import") (part "22-?-0527-2051"))
    )
    (comp (ref "J3")
      (value "22-27-2021-02")
      (footprint "eagle-import:6410-02")
      (libsource (lib "eagle-import") (part "22-?-0227-2021"))
    )
    (comp (ref "J4")
      (value "22-27-2051-05")
      (footprint "eagle-import:6410-05")
      (libsource (lib "eagle-import") (part "22-?-0527-2051"))
    )
    (comp (ref "J5")
      (value "22-27-2021-02")
      (footprint "eagle-import:6410-02")
      (libsource (lib "eagle-import") (part "22-?-0227-2021"))
    )
    (comp (ref "R25")
      (value "RD")
      (footprint "eagle-import:R0805")
      (libsource (lib "eagle-import") (part "R-US_R0805"))
    )
    (comp (ref "R26")
      (value "RC")
      (footprint "eagle-import:R0805")
      (libsource (lib "eagle-import") (part "R-US_R0805"))
    )
    (comp (ref "R27")
      (value "RA")
      (footprint "eagle-import:R0805")
      (libsource (lib "eagle-import") (part "R-US_R0805"))
    )
    (comp (ref "R28")
      (value "RB")
      (footprint "eagle-import:R0805")
      (libsource (lib "eagle-import") (part "R-US_R0805"))
    )
    (comp (ref "R29")
      (value "4K7")
      (footprint "eagle-import:R0805")
      (libsource (lib "eagle-import") (part "R-US_R0805"))
    )
    (comp (ref "R30")
      (value "RD")
      (footprint "eagle-import:R0805")
      (libsource (lib "eagle-import") (part "R-US_R0805"))
    )
    (comp (ref "R31")
      (value "RC")
      (footprint "eagle-import:R0805")
      (libsource (lib "eagle-import") (part "R-US_R0805"))
    )
    (comp (ref "R32")
      (value "RA")
      (footprint "eagle-import:R0805")
      (libsource (lib "eagle-import") (part "R-US_R0805"))
    )
    (comp (ref "R33")
      (value "RB")
      (footprint "eagle-import:R0805")
      (libsource (lib "eagle-import") (part "R-US_R0805"))
    )
    (comp (ref "R34")
      (value "4K7")
      (footprint "eagle-import:R0805")
      (libsource (lib "eagle-import") (part "R-US_R0805"))
    )
    (comp (ref "J6")
      (value "22-27-2031-03")
      (footprint "eagle-import:6410-03")
      (libsource (lib "eagle-import") (part "22-?-0327-2031"))
    )
    (comp (ref "J7")
      (value "22-27-2031-03")
      (footprint "eagle-import:6410-03")
      (libsource (lib "eagle-import") (part "22-?-0327-2031"))
    )
    (comp (ref "J8")
      (value "22-27-2031-03")
      (footprint "eagle-import:6410-03")
      (libsource (lib "eagle-import") (part "22-?-0327-2031"))
    )
    (comp (ref "J9")
      (value "22-27-2031-03")
      (footprint "eagle-import:6410-03")
      (libsource (lib "eagle-import") (part "22-?-0327-2031"))
    )
    (comp (ref "J10")
      (value "22-27-2031-03")
      (footprint "eagle-import:6410-03")
      (libsource (lib "eagle-import") (part "22-?-0327-2031"))
    )
    (comp (ref "J11")
      (value "22-27-2031-03")
      (footprint "eagle-import:6410-03")
      (libsource (lib "eagle-import") (part "22-?-0327-2031"))
    )
    (comp (ref "J12")
      (value "22-27-2041-04")
      (footprint "eagle-import:6410-04")
      (libsource (lib "eagle-import") (part "22-?-0427-2041"))
    )
    (comp (ref "J13")
      (value "22-27-2041-04")
      (footprint "eagle-import:6410-04")
      (libsource (lib "eagle-import") (part "22-?-0427-2041"))
    )
    (comp (ref "J14")
      (value "22-27-2041-04")
      (footprint "eagle-import:6410-04")
      (libsource (lib "eagle-import") (part "22-?-0427-2041"))
    )
    (comp (ref "J15")
      (value "22-27-2031-03")
      (footprint "eagle-import:6410-03")
      (libsource (lib "eagle-import") (part "22-?-0327-2031"))
    )
    (comp (ref "R35")
      (value "NC")
      (footprint "eagle-import:R0805")
      (libsource (lib "eagle-import") (part "R-US_R0805"))
    )
    (comp (ref "R36")
      (value "4K7")
      (footprint "eagle-import:R0805")
      (libsource (lib "eagle-import") (part "R-US_R0805"))
    )
    (comp (ref "R37")
      (value "NC")
      (footprint "eagle-import:R0805")
      (libsource (lib "eagle-import") (part "R-US_R0805"))
    )
    (comp (ref "R38")
      (value "4K7")
      (footprint "eagle-import:R0805")
      (libsource (lib "eagle-import") (part "R-US_R0805"))
    )
    (comp (ref "R39")
      (value "NC")
      (footprint "eagle-import:R0805")
      (libsource (lib "eagle-import") (part "R-US_R0805"))
    )
    (comp (ref "R40")
      (value "4K7")
      (footprint "eagle-import:R0805")
      (libsource (lib "eagle-import") (part "R-US_R0805"))
    )
    (comp (ref "R41")
      (value "NC")
      (footprint "eagle-import:R0805")
      (libsource (lib "eagle-import") (part "R-US_R0805"))
    )
    (comp (ref "R42")
      (value "4K7")
      (footprint "eagle-import:R0805")
      (libsource (lib "eagle-import") (part "R-US_R0805"))
    )
    (comp (ref "R43")
      (value "NC")
      (footprint "eagle-import:R0805")
      (libsource (lib "eagle-import") (part "R-US_R0805"))
    )
    (comp (ref "R44")
      (value "4K7")
      (footprint "eagle-import:R0805")
      (libsource (lib "eagle-import") (part "R-US_R0805"))
    )
    (comp (ref "R45")
      (value "NC")
      (footprint "eagle-import:R0805")
      (libsource (lib "eagle-import") (part "R-US_R0805"))
    )
    (comp (ref "R46")
      (value "4K7")
      (footprint "eagle-import:R0805")
      (libsource (lib "eagle-import") (part "R-US_R0805"))
    )
    (comp (ref "R47")
      (value "NC")
      (footprint "eagle-import:R0805")
      (libsource (lib "eagle-import") (part "R-US_R0805"))
    )
    (comp (ref "R48")
      (value "4K7")
      (footprint "eagle-import:R0805")
      (libsource (lib "eagle-import") (part "R-US_R0805"))
    )
    (comp (ref "SV1")
      (value "ML10")
      (footprint "eagle-import:ML10")
      (libsource (lib "eagle-import") (part "ML10"))
    )
    (comp (ref "C14")
      (value "100nF")
      (footprint "eagle-import:C0603")
      (libsource (lib "eagle-import") (part "C-EUC0603"))
    )
    (comp (ref "C15")
      (value "10uF/6V/lowESR")
      (footprint "eagle-import:SMC_A")
      (libsource (lib "eagle-import") (part "CPOL-USSMCA"))
    )
    (comp (ref "C16")
      (value "100nF")
      (footprint "eagle-import:C0603")
      (libsource (lib "eagle-import") (part "C-EUC0603"))
    )
    (comp (ref "C17")
      (value "22pF")
      (footprint "eagle-import:C0805")
      (libsource (lib "eagle-import") (part "C-EUC0805"))
    )
    (comp (ref "C18")
      (value "22pF")
      (footprint "eagle-import:C0805")
      (libsource (lib "eagle-import") (part "C-EUC0805"))
    )
    (comp (ref "C19")
      (value "100nF")
      (footprint "eagle-import:C0603")
      (libsource (lib "eagle-import") (part "C-EUC0603"))
    )
    (comp (ref "CN1")
      (value "HDR-1X5-SIP-100")
      (footprint "eagle-import:SIP-100-5V")
      (libsource (lib "eagle-import") (part "HDR-1X5-SIP-100"))
    )
    (comp (ref "IC4")
      (value "DSPIC33FJ128MC804-I/PT")
      (footprint "eagle-import:TQFP44")
      (libsource (lib "eagle-import") (part "DSPIC33FJXXMC804SMD"))
    )
    (comp (ref "J1")
      (value "22-27-2031-03")
      (footprint "eagle-import:6410-03")
      (libsource (lib "eagle-import") (part "22-?-0327-2031"))
    )
    (comp (ref "JP1")
      (value "JP2E")
      (footprint "eagle-import:JP2")
      (libsource (lib "eagle-import") (part "JP2E"))
    )
    (comp (ref "LED6")
      (value "Red")
      (footprint "eagle-import:CHIP-LED0805")
      (libsource (lib "eagle-import") (part "LEDCHIP-LED0805"))
    )
    (comp (ref "LED7")
      (value "Red")
      (footprint "eagle-import:CHIP-LED0805")
      (libsource (lib "eagle-import") (part "LEDCHIP-LED0805"))
    )
    (comp (ref "LED8")
      (value "Red")
      (footprint "eagle-import:CHIP-LED0805")
      (libsource (lib "eagle-import") (part "LEDCHIP-LED0805"))
    )
    (comp (ref "LED9")
      (value "Red")
      (footprint "eagle-import:CHIP-LED0805")
      (libsource (lib "eagle-import") (part "LEDCHIP-LED0805"))
    )
    (comp (ref "Q1")
      (value "10MHz")
      (footprint "eagle-import:HC49UP")
      (libsource (lib "eagle-import") (part "CRYSTALHC49UP"))
    )
    (comp (ref "R14")
      (value "270R")
      (footprint "eagle-import:R0805")
      (libsource (lib "eagle-import") (part "R-US_R0805"))
    )
    (comp (ref "R15")
      (value "270R")
      (footprint "eagle-import:R0805")
      (libsource (lib "eagle-import") (part "R-US_R0805"))
    )
    (comp (ref "R16")
      (value "4K7")
      (footprint "eagle-import:R0805")
      (libsource (lib "eagle-import") (part "R-US_R0805"))
    )
    (comp (ref "R17")
      (value "4K7")
      (footprint "eagle-import:R0805")
      (libsource (lib "eagle-import") (part "R-US_R0805"))
    )
    (comp (ref "R18")
      (value "270R")
      (footprint "eagle-import:R0805")
      (libsource (lib "eagle-import") (part "R-US_R0805"))
    )
    (comp (ref "R19")
      (value "270R")
      (footprint "eagle-import:R0805")
      (libsource (lib "eagle-import") (part "R-US_R0805"))
    )
    (comp (ref "R20")
      (value "0R")
      (footprint "eagle-import:R0805")
      (libsource (lib "eagle-import") (part "R-US_R0805"))
    )
    (comp (ref "R21")
      (value "10K")
      (footprint "eagle-import:R0805")
      (libsource (lib "eagle-import") (part "R-US_R0805"))
    )
    (comp (ref "R22")
      (value "4K7")
      (footprint "eagle-import:R0805")
      (libsource (lib "eagle-import") (part "R-US_R0805"))
    )
    (comp (ref "S1")
      (value "10-XX")
      (footprint "eagle-import:B3F-10XX")
      (libsource (lib "eagle-import") (part "10-XX"))
    )
    (comp (ref "C1")
      (value "100nF")
      (footprint "eagle-import:C0805")
      (libsource (lib "eagle-import") (part "C-EUC0805"))
    )
    (comp (ref "C2")
      (value "220uF/10V")
      (footprint "eagle-import:E2,5-7")
      (libsource (lib "eagle-import") (part "CPOL-USE2.5-7"))
    )
    (comp (ref "C3")
      (value "47uF/6V")
      (footprint "eagle-import:SMC_D")
      (libsource (lib "eagle-import") (part "CPOL-USSMCD"))
    )
    (comp (ref "C4")
      (value "100nF")
      (footprint "eagle-import:C0805")
      (libsource (lib "eagle-import") (part "C-EUC0805"))
    )
    (comp (ref "C5")
      (value "10uF/10V")
      (footprint "eagle-import:C1206")
      (libsource (lib "eagle-import") (part "C-EUC1206"))
    )
    (comp (ref "C6")
      (value "100nF")
      (footprint "eagle-import:C0805")
      (libsource (lib "eagle-import") (part "C-EUC0805"))
    )
    (comp (ref "C7")
      (value "100nF")
      (footprint "eagle-import:C0805")
      (libsource (lib "eagle-import") (part "C-EUC0805"))
    )
    (comp (ref "C8")
      (value "220uF/35V")
      (footprint "eagle-import:E5-10,5")
      (libsource (lib "eagle-import") (part "CPOL-USE5-10.5"))
    )
    (comp (ref "C9")
      (value "100nF")
      (footprint "eagle-import:C0805")
      (libsource (lib "eagle-import") (part "C-EUC0805"))
    )
    (comp (ref "C10")
      (value "220uF/35V")
      (footprint "eagle-import:E5-10,5")
      (libsource (lib "eagle-import") (part "CPOL-USE5-10.5"))
    )
    (comp (ref "C11")
      (value "100nF")
      (footprint "eagle-import:C0805")
      (libsource (lib "eagle-import") (part "C-EUC0805"))
    )
    (comp (ref "C12")
      (value "47uF/16V")
      (footprint "eagle-import:SMC_D")
      (libsource (lib "eagle-import") (part "CPOL-USSMCD"))
    )
    (comp (ref "C13")
      (value "100nF")
      (footprint "eagle-import:C0805")
      (libsource (lib "eagle-import") (part "C-EUC0805"))
    )
    (comp (ref "F1")
      (value "FUSETE5")
      (footprint "eagle-import:TE5")
      (libsource (lib "eagle-import") (part "FUSETE5"))
    )
    (comp (ref "F2")
      (value "FUSETE5")
      (footprint "eagle-import:TE5")
      (libsource (lib "eagle-import") (part "FUSETE5"))
    )
    (comp (ref "IC1")
      (value "LM1086CT-3.3")
      (footprint "eagle-import:317TS")
      (libsource (lib "eagle-import") (part "LM317TS"))
    )
    (comp (ref "IC2")
      (value "ADR443BRZ-R-8")
      (footprint "eagle-import:SOIC8")
      (libsource (lib "eagle-import") (part "ADR443"))
    )
    (comp (ref "IC3")
      (value "LM338T")
      (footprint "eagle-import:317TS")
      (libsource (lib "eagle-import") (part "LM317TS"))
    )
    (comp (ref "LED1")
      (value "Green")
      (footprint "eagle-import:CHIP-LED0805")
      (libsource (lib "eagle-import") (part "LEDCHIP-LED0805"))
    )
    (comp (ref "LED2")
      (value "Green")
      (footprint "eagle-import:CHIP-LED0805")
      (libsource (lib "eagle-import") (part "LEDCHIP-LED0805"))
    )
    (comp (ref "LED3")
      (value "Green")
      (footprint "eagle-import:CHIP-LED0805")
      (libsource (lib "eagle-import") (part "LEDCHIP-LED0805"))
    )
    (comp (ref "LED4")
      (value "Green")
      (footprint "eagle-import:CHIP-LED0805")
      (libsource (lib "eagle-import") (part "LEDCHIP-LED0805"))
    )
    (comp (ref "LED5")
      (value "LEDCHIP-LED0805")
      (footprint "eagle-import:CHIP-LED0805")
      (libsource (lib "eagle-import") (part "LEDCHIP-LED0805"))
    )
    (comp (ref "R1")
      (value "0R")
      (footprint "eagle-import:R0805")
      (libsource (lib "eagle-import") (part "R-US_R0805"))
    )
    (comp (ref "R2")
      (value "0R")
      (footprint "eagle-import:R0805")
      (libsource (lib "eagle-import") (part "R-US_R0805"))
    )
    (comp (ref "R3")
      (value "470R")
      (footprint "eagle-import:R0805")
      (libsource (lib "eagle-import") (part "R-US_R0805"))
    )
    (comp (ref "R4")
      (value "270R")
      (footprint "eagle-import:R0805")
      (libsource (lib "eagle-import") (part "R-US_R0805"))
    )
    (comp (ref "R5")
      (value "0R")
      (footprint "eagle-import:R0805")
      (libsource (lib "eagle-import") (part "R-US_R0805"))
    )
    (comp (ref "R6")
      (value "0R")
      (footprint "eagle-import:R0805")
      (libsource (lib "eagle-import") (part "R-US_R0805"))
    )
    (comp (ref "R7")
      (value "0R")
      (footprint "eagle-import:R0805")
      (libsource (lib "eagle-import") (part "R-US_R0805"))
    )
    (comp (ref "R8")
      (value "240R/1%")
      (footprint "eagle-import:R0805")
      (libsource (lib "eagle-import") (part "R-US_R0805"))
    )
    (comp (ref "R9")
      (value "2K7")
      (footprint "eagle-import:R0805")
      (libsource (lib "eagle-import") (part "R-US_R0805"))
    )
    (comp (ref "R10")
      (value "1K")
      (footprint "eagle-import:R0805")
      (libsource (lib "eagle-import") (part "R-US_R0805"))
    )
    (comp (ref "R11")
      (value "1K")
      (footprint "eagle-import:R0805")
      (libsource (lib "eagle-import") (part "R-US_R0805"))
    )
    (comp (ref "R12")
      (value "1K6/1%")
      (footprint "eagle-import:R0805")
      (libsource (lib "eagle-import") (part "R-US_R0805"))
    )
    (comp (ref "R13")
      (value "0R")
      (footprint "eagle-import:R0805")
      (libsource (lib "eagle-import") (part "R-US_R0805"))
    )
    (comp (ref "X1")
      (value "W237-02P")
      (footprint "eagle-import:W237-132")
      (libsource (lib "eagle-import") (part "W237-02P"))
    )
    (comp (ref "X2")
      (value "W237-02P")
      (footprint "eagle-import:W237-132")
      (libsource (lib "eagle-import") (part "W237-02P"))
    )
    (comp (ref "X3")
      (value "W237-02P")
      (footprint "eagle-import:W237-132")
      (libsource (lib "eagle-import") (part "W237-02P"))
    )
  )
  (nets
    (net (code "1") (name "+3V3") (class "Default")
      (node (ref "C14") (pin "1") (pinfunction "1_1") (pintype "passive"))
      (node (ref "C16") (pin "1") (pinfunction "1_1") (pintype "passive"))
      (node (ref "C19") (pin "1") (pinfunction "1_1") (pintype "passive"))
      (node (ref "C20") (pin "1") (pinfunction "1_1") (pintype "passive"))
      (node (ref "C22") (pin "1") (pinfunction "1_1") (pintype "passive"))
      (node (ref "C25") (pin "1") (pinfunction "1_1") (pintype "passive"))
      (node (ref "C3") (pin "+") (pinfunction "+_+") (pintype "passive"))
      (node (ref "C4") (pin "1") (pinfunction "1_1") (pintype "passive"))
      (node (ref "C44") (pin "2") (pinfunction "2_2") (pintype "passive"))
      (node (ref "C45") (pin "2") (pinfunction "2_2") (pintype "passive"))
      (node (ref "CN1") (pin "2") (pinfunction "2_2") (pintype "passive"))
      (node (ref "IC1") (pin "2") (pinfunction "OUT_2") (pintype "passive"))
      (node (ref "IC19") (pin "16") (pinfunction "VDD_16") (pintype "passive"))
      (node (ref "IC19") (pin "2") (pinfunction "VDD_2") (pintype "passive"))
      (node (ref "IC20") (pin "16") (pinfunction "VDD_16") (pintype "passive"))
      (node (ref "IC20") (pin "2") (pinfunction "VDD_2") (pintype "passive"))
      (node (ref "IC21") (pin "16") (pinfunction "VCC_16") (pintype "power_in"))
      (node (ref "IC4") (pin "17") (pinfunction "AVDD_17") (pintype "passive"))
      (node (ref "IC4") (pin "28") (pinfunction "VDD_28") (pintype "passive"))
      (node (ref "IC4") (pin "40") (pinfunction "VDD_40") (pintype "passive"))
      (node (ref "IC5") (pin "17") (pinfunction "AVDD_17") (pintype "passive"))
      (node (ref "IC5") (pin "28") (pinfunction "VDD_28") (pintype "passive"))
      (node (ref "IC5") (pin "40") (pinfunction "VDD_40") (pintype "passive"))
      (node (ref "LED10") (pin "A") (pinfunction "A_A") (pintype "passive"))
      (node (ref "LED2") (pin "A") (pinfunction "A_A") (pintype "passive"))
      (node (ref "LED6") (pin "A") (pinfunction "A_A") (pintype "passive"))
      (node (ref "LED7") (pin "A") (pinfunction "A_A") (pintype "passive"))
      (node (ref "LED8") (pin "A") (pinfunction "A_A") (pintype "passive"))
      (node (ref "LED9") (pin "A") (pinfunction "A_A") (pintype "passive"))
      (node (ref "R21") (pin "2") (pinfunction "2_2") (pintype "passive"))
    )
    (net (code "2") (name "+3V_VREF") (class "Default")
      (node (ref "C7") (pin "1") (pinfunction "1_1") (pintype "passive"))
      (node (ref "IC2") (pin "6") (pinfunction "NC_6") (pintype "passive"))
      (node (ref "IC4") (pin "19") (pinfunction "AN0/VREF+/CN2/RA0_19") (pintype "passive"))
      (node (ref "IC5") (pin "19") (pinfunction "AN0/VREF+/CN2/RA0_19") (pintype "passive"))
      (node (ref "R26") (pin "1") (pinfunction "1_1") (pintype "passive"))
      (node (ref "R31") (pin "1") (pinfunction "1_1") (pintype "passive"))
      (node (ref "R81") (pin "2") (pinfunction "2_2") (pintype "passive"))
    )
    (net (code "3") (name "+5V") (class "Default")
      (node (ref "C1") (pin "1") (pinfunction "1_1") (pintype "passive"))
      (node (ref "C2") (pin "+") (pinfunction "+_+") (pintype "passive"))
      (node (ref "F1") (pin "2") (pinfunction "2_2") (pintype "passive"))
      (node (ref "IC1") (pin "3") (pinfunction "IN_3") (pintype "input"))
      (node (ref "J1") (pin "2") (pinfunction "S_2") (pintype "passive"))
      (node (ref "J12") (pin "2") (pinfunction "S_2") (pintype "passive"))
      (node (ref "J13") (pin "2") (pinfunction "S_2") (pintype "passive"))
      (node (ref "J14") (pin "2") (pinfunction "S_2") (pintype "passive"))
      (node (ref "LED1") (pin "A") (pinfunction "A_A") (pintype "passive"))
      (node (ref "R16") (pin "2") (pinfunction "2_2") (pintype "passive"))
      (node (ref "R17") (pin "2") (pinfunction "2_2") (pintype "passive"))
      (node (ref "R2") (pin "2") (pinfunction "2_2") (pintype "passive"))
      (node (ref "R22") (pin "2") (pinfunction "2_2") (pintype "passive"))
      (node (ref "R29") (pin "2") (pinfunction "2_2") (pintype "passive"))
      (node (ref "R34") (pin "2") (pinfunction "2_2") (pintype "passive"))
      (node (ref "R36") (pin "2") (pinfunction "2_2") (pintype "passive"))
      (node (ref "R38") (pin "2") (pinfunction "2_2") (pintype "passive"))
      (node (ref "R40") (pin "2") (pinfunction "2_2") (pintype "passive"))
      (node (ref "R42") (pin "2") (pinfunction "2_2") (pintype "passive"))
      (node (ref "R44") (pin "2") (pinfunction "2_2") (pintype "passive"))
      (node (ref "R46") (pin "2") (pinfunction "2_2") (pintype "passive"))
      (node (ref "R48") (pin "2") (pinfunction "2_2") (pintype "passive"))
      (node (ref "R49") (pin "2") (pinfunction "2_2") (pintype "passive"))
      (node (ref "R50") (pin "2") (pinfunction "2_2") (pintype "passive"))
      (node (ref "R51") (pin "2") (pinfunction "2_2") (pintype "passive"))
      (node (ref "R52") (pin "2") (pinfunction "2_2") (pintype "passive"))
      (node (ref "R53") (pin "2") (pinfunction "2_2") (pintype "passive"))
      (node (ref "R54") (pin "2") (pinfunction "2_2") (pintype "passive"))
      (node (ref "R55") (pin "2") (pinfunction "2_2") (pintype "passive"))
      (node (ref "R56") (pin "2") (pinfunction "2_2") (pintype "passive"))
      (node (ref "R61") (pin "2") (pinfunction "2_2") (pintype "passive"))
      (node (ref "R62") (pin "2") (pinfunction "2_2") (pintype "passive"))
      (node (ref "R63") (pin "2") (pinfunction "2_2") (pintype "passive"))
      (node (ref "R64") (pin "2") (pinfunction "2_2") (pintype "passive"))
      (node (ref "SV1") (pin "8") (pinfunction "8_8") (pintype "passive"))
    )
    (net (code "4") (name "+5V_ANALOG") (class "Default")
      (node (ref "C27") (pin "1") (pinfunction "1_1") (pintype "passive"))
      (node (ref "C28") (pin "2") (pinfunction "2_2") (pintype "passive"))
      (node (ref "C33") (pin "1") (pinfunction "1_1") (pintype "passive"))
      (node (ref "C34") (pin "2") (pinfunction "2_2") (pintype "passive"))
      (node (ref "C35") (pin "2") (pinfunction "2_2") (pintype "passive"))
      (node (ref "C37") (pin "2") (pinfunction "2_2") (pintype "passive"))
      (node (ref "C39") (pin "1") (pinfunction "1_1") (pintype "passive"))
      (node (ref "C40") (pin "2") (pinfunction "2_2") (pintype "passive"))
      (node (ref "C41") (pin "2") (pinfunction "2_2") (pintype "passive"))
      (node (ref "C5") (pin "1") (pinfunction "1_1") (pintype "passive"))
      (node (ref "C6") (pin "1") (pinfunction "1_1") (pintype "passive"))
      (node (ref "IC14") (pin "8") (pinfunction "V+_8") (pintype "power_in"))
      (node (ref "IC15") (pin "8") (pinfunction "VCC_8") (pintype "power_in"))
      (node (ref "IC16") (pin "8") (pinfunction "VCC_8") (pintype "power_in"))
      (node (ref "IC17") (pin "8") (pinfunction "V+_8") (pintype "power_in"))
      (node (ref "IC18") (pin "8") (pinfunction "VCC_8") (pintype "power_in"))
      (node (ref "IC2") (pin "2") (pinfunction "VIN_2") (pintype "passive"))
      (node (ref "IC6") (pin "8") (pinfunction "V+_8") (pintype "power_in"))
      (node (ref "R2") (pin "1") (pinfunction "1_1") (pintype "passive"))
    )
    (net (code "5") (name "+12V") (class "Default")
      (node (ref "F2") (pin "2") (pinfunction "2_2") (pintype "passive"))
      (node (ref "J10") (pin "2") (pinfunction "S_2") (pintype "passive"))
      (node (ref "J11") (pin "2") (pinfunction "S_2") (pintype "passive"))
      (node (ref "J15") (pin "2") (pinfunction "S_2") (pintype "passive"))
      (node (ref "J2") (pin "2") (pinfunction "S_2") (pintype "passive"))
      (node (ref "J4") (pin "2") (pinfunction "S_2") (pintype "passive"))
      (node (ref "J6") (pin "2") (pinfunction "S_2") (pintype "passive"))
      (node (ref "J7") (pin "2") (pinfunction "S_2") (pintype "passive"))
      (node (ref "J8") (pin "2") (pinfunction "S_2") (pintype "passive"))
      (node (ref "J9") (pin "2") (pinfunction "S_2") (pintype "passive"))
      (node (ref "LED4") (pin "A") (pinfunction "A_A") (pintype "passive"))
      (node (ref "SV1") (pin "1") (pinfunction "1_1") (pintype "passive"))
      (node (ref "SV1") (pin "9") (pinfunction "9_9") (pintype "passive"))
    )
    (net (code "6") (name "+24V") (class "Default")
      (node (ref "C30") (pin "2") (pinfunction "2_2") (pintype "passive"))
      (node (ref "C31") (pin "2") (pinfunction "2_2") (pintype "passive"))
      (node (ref "C32") (pin "2") (pinfunction "2_2") (pintype "passive"))
      (node (ref "C8") (pin "+") (pinfunction "+_+") (pintype "passive"))
      (node (ref "C9") (pin "1") (pinfunction "1_1") (pintype "passive"))
      (node (ref "D1") (pin "K") (pinfunction "K_K") (pintype "passive"))
      (node (ref "D2") (pin "K") (pinfunction "K_K") (pintype "passive"))
      (node (ref "IC10") (pin "6") (pinfunction "VDD_6") (pintype "power_in"))
      (node (ref "IC11") (pin "6") (pinfunction "VDD_6") (pintype "power_in"))
      (node (ref "IC12") (pin "3") (pinfunction "S_3") (pintype "bidirectional"))
      (node (ref "IC13") (pin "3") (pinfunction "S_3") (pintype "bidirectional"))
      (node (ref "IC7") (pin "6") (pinfunction "VDD_6") (pintype "power_in"))
      (node (ref "IC8") (pin "3") (pinfunction "S_3") (pintype "bidirectional"))
      (node (ref "IC9") (pin "3") (pinfunction "S_3") (pintype "bidirectional"))
      (node (ref "K1") (pin "1") (pinfunction "1_1") (pintype "passive"))
      (node (ref "LED3") (pin "A") (pinfunction "A_A") (pintype "passive"))
      (node (ref "X10") (pin "2") (pinfunction "KL_2") (pintype "passive"))
      (node (ref "X11") (pin "2") (pinfunction "KL_2") (pintype "passive"))
      (node (ref "X3") (pin "2") (pinfunction "KL_2") (pintype "passive"))
      (node (ref "X7") (pin "2") (pinfunction "KL_2") (pintype "passive"))
      (node (ref "X9") (pin "2") (pinfunction "KL_2") (pintype "passive"))
    )
    (net (code "7") (name "0V") (class "Default")
      (node (ref "C30") (pin "1") (pinfunction "1_1") (pintype "passive"))
      (node (ref "C31") (pin "1") (pinfunction "1_1") (pintype "passive"))
      (node (ref "C32") (pin "1") (pinfunction "1_1") (pintype "passive"))
      (node (ref "C8") (pin "-") (pinfunction "-_-") (pintype "passive"))
      (node (ref "C9") (pin "2") (pinfunction "2_2") (pintype "passive"))
      (node (ref "IC10") (pin "3") (pinfunction "GND_3") (pintype "power_in"))
      (node (ref "IC11") (pin "3") (pinfunction "GND_3") (pintype "power_in"))
      (node (ref "IC12") (pin "1") (pinfunction "S_1") (pintype "bidirectional"))
      (node (ref "IC13") (pin "1") (pinfunction "S_1") (pintype "bidirectional"))
      (node (ref "IC15") (pin "3") (pinfunction "IP-_3") (pintype "passive"))
      (node (ref "IC15") (pin "4") (pinfunction "IP-_4") (pintype "passive"))
      (node (ref "IC16") (pin "3") (pinfunction "IP-_3") (pintype "passive"))
      (node (ref "IC16") (pin "4") (pinfunction "IP-_4") (pintype "passive"))
      (node (ref "IC18") (pin "3") (pinfunction "IP-_3") (pintype "passive"))
      (node (ref "IC18") (pin "4") (pinfunction "IP-_4") (pintype "passive"))
      (node (ref "IC7") (pin "3") (pinfunction "GND_3") (pintype "power_in"))
      (node (ref "IC8") (pin "1") (pinfunction "S_1") (pintype "bidirectional"))
      (node (ref "IC9") (pin "1") (pinfunction "S_1") (pintype "bidirectional"))
      (node (ref "R59") (pin "1") (pinfunction "1_1") (pintype "passive"))
      (node (ref "R60") (pin "1") (pinfunction "1_1") (pintype "passive"))
      (node (ref "R67") (pin "2") (pinfunction "2_2") (pintype "passive"))
      (node (ref "R68") (pin "1") (pinfunction "1_1") (pintype "passive"))
      (node (ref "R69") (pin "1") (pinfunction "1_1") (pintype "passive"))
      (node (ref "R79") (pin "1") (pinfunction "1_1") (pintype "passive"))
      (node (ref "R9") (pin "1") (pinfunction "1_1") (pintype "passive"))
      (node (ref "X3") (pin "1") (pinfunction "KL_1") (pintype "passive"))
    )
    (net (code "8") (name "AGND") (class "Default")
      (node (ref "C26") (pin "2") (pinfunction "2_2") (pintype "passive"))
      (node (ref "C27") (pin "2") (pinfunction "2_2") (pintype "passive"))
      (node (ref "C28") (pin "1") (pinfunction "1_1") (pintype "passive"))
      (node (ref "C29") (pin "2") (pinfunction "2_2") (pintype "passive"))
      (node (ref "C33") (pin "2") (pinfunction "2_2") (pintype "passive"))
      (node (ref "C34") (pin "1") (pinfunction "1_1") (pintype "passive"))
      (node (ref "C35") (pin "1") (pinfunction "1_1") (pintype "passive"))
      (node (ref "C36") (pin "1") (pinfunction "1_1") (pintype "passive"))
      (node (ref "C37") (pin "1") (pinfunction "1_1") (pintype "passive"))
      (node (ref "C38") (pin "1") (pinfunction "1_1") (pintype "passive"))
      (node (ref "C39") (pin "2") (pinfunction "2_2") (pintype "passive"))
      (node (ref "C40") (pin "1") (pinfunction "1_1") (pintype "passive"))
      (node (ref "C41") (pin "1") (pinfunction "1_1") (pintype "passive"))
      (node (ref "C42") (pin "1") (pinfunction "1_1") (pintype "passive"))
      (node (ref "C5") (pin "2") (pinfunction "2_2") (pintype "passive"))
      (node (ref "C6") (pin "2") (pinfunction "2_2") (pintype "passive"))
      (node (ref "C7") (pin "2") (pinfunction "2_2") (pintype "passive"))
      (node (ref "IC14") (pin "4") (pinfunction "V-_4") (pintype "power_in"))
      (node (ref "IC15") (pin "5") (pinfunction "GND_5") (pintype "power_in"))
      (node (ref "IC16") (pin "5") (pinfunction "GND_5") (pintype "power_in"))
      (node (ref "IC17") (pin "4") (pinfunction "V-_4") (pintype "power_in"))
      (node (ref "IC18") (pin "5") (pinfunction "GND_5") (pintype "power_in"))
      (node (ref "IC2") (pin "4") (pinfunction "GND_4") (pintype "passive"))
      (node (ref "IC4") (pin "20") (pinfunction "AN1/VREF-/CN3/RA1_20") (pintype "passive"))
      (node (ref "IC5") (pin "20") (pinfunction "AN1/VREF-/CN3/RA1_20") (pintype "passive"))
      (node (ref "IC6") (pin "4") (pinfunction "V-_4") (pintype "power_in"))
      (node (ref "J2") (pin "4") (pinfunction "S_4") (pintype "passive"))
      (node (ref "J4") (pin "4") (pinfunction "S_4") (pintype "passive"))
      (node (ref "R20") (pin "1") (pinfunction "1_1") (pintype "passive"))
      (node (ref "R24") (pin "1") (pinfunction "1_1") (pintype "passive"))
      (node (ref "R28") (pin "1") (pinfunction "1_1") (pintype "passive"))
      (node (ref "R33") (pin "1") (pinfunction "1_1") (pintype "passive"))
      (node (ref "R7") (pin "1") (pinfunction "1_1") (pintype "passive"))
      (node (ref "R85") (pin "1") (pinfunction "1_1") (pintype "passive"))
    )
    (net (code "9") (name "BEACON_UART_RX") (class "Default")
      (node (ref "IC20") (pin "26") (pinfunction "TXD_26") (pintype "passive"))
      (node (ref "IC4") (pin "1") (pinfunction "SDA1/RP9*/CN21/PMD3/RB9_1") (pintype "passive"))
    )
    (net (code "10") (name "BEACON_UART_TX") (class "Default")
      (node (ref "IC20") (pin "6") (pinfunction "RXD_6") (pintype "passive"))
      (node (ref "IC4") (pin "5") (pinfunction "RP25*/CN19/PMA6/RC9_5") (pintype "passive"))
    )
    (net (code "11") (name "FROM_TX_RS232_M") (class "Default")
      (node (ref "CON1") (pin "3") (pinfunction "3_3") (pintype "passive"))
      (node (ref "IC21") (pin "13") (pinfunction "R1IN_13") (pintype "input"))
    )
    (net (code "12") (name "GND") (class "Default")
      (node (ref "C14") (pin "2") (pinfunction "2_2") (pintype "passive"))
      (node (ref "C15") (pin "-") (pinfunction "-_-") (pintype "passive"))
      (node (ref "C16") (pin "2") (pinfunction "2_2") (pintype "passive"))
      (node (ref "C17") (pin "2") (pinfunction "2_2") (pintype "passive"))
      (node (ref "C18") (pin "2") (pinfunction "2_2") (pintype "passive"))
      (node (ref "C19") (pin "2") (pinfunction "2_2") (pintype "passive"))
      (node (ref "C20") (pin "2") (pinfunction "2_2") (pintype "passive"))
      (node (ref "C21") (pin "-") (pinfunction "-_-") (pintype "passive"))
      (node (ref "C22") (pin "2") (pinfunction "2_2") (pintype "passive"))
      (node (ref "C23") (pin "2") (pinfunction "2_2") (pintype "passive"))
      (node (ref "C24") (pin "2") (pinfunction "2_2") (pintype "passive"))
      (node (ref "C25") (pin "2") (pinfunction "2_2") (pintype "passive"))
      (node (ref "C3") (pin "-") (pinfunction "-_-") (pintype "passive"))
      (node (ref "C4") (pin "2") (pinfunction "2_2") (pintype "passive"))
      (node (ref "C45") (pin "1") (pinfunction "1_1") (pintype "passive"))
      (node (ref "C47") (pin "1") (pinfunction "1_1") (pintype "passive"))
      (node (ref "CN1") (pin "3") (pinfunction "3_3") (pintype "passive"))
      (node (ref "CON1") (pin "5") (pinfunction "5_5") (pintype "passive"))
      (node (ref "IC1") (pin "1") (pinfunction "ADJ_1") (pintype "input"))
      (node (ref "IC19") (pin "1") (pinfunction "GND_1") (pintype "passive"))
      (node (ref "IC19") (pin "14") (pinfunction "GND_14") (pintype "passive"))
      (node (ref "IC19") (pin "15") (pinfunction "GND_15") (pintype "passive"))
      (node (ref "IC19") (pin "17") (pinfunction "RES_17") (pintype "passive"))
      (node (ref "IC19") (pin "28") (pinfunction "GND_28") (pintype "passive"))
      (node (ref "IC20") (pin "1") (pinfunction "GND_1") (pintype "passive"))
      (node (ref "IC20") (pin "14") (pinfunction "GND_14") (pintype "passive"))
      (node (ref "IC20") (pin "15") (pinfunction "GND_15") (pintype "passive"))
      (node (ref "IC20") (pin "17") (pinfunction "RES_17") (pintype "passive"))
      (node (ref "IC20") (pin "28") (pinfunction "GND_28") (pintype "passive"))
      (node (ref "IC21") (pin "10") (pinfunction "T2IN_10") (pintype "input"))
      (node (ref "IC21") (pin "15") (pinfunction "GND_15") (pintype "power_in"))
      (node (ref "IC21") (pin "8") (pinfunction "R2IN_8") (pintype "input"))
      (node (ref "IC4") (pin "16") (pinfunction "AVSS_16") (pintype "passive"))
      (node (ref "IC4") (pin "29") (pinfunction "VSS_29") (pintype "passive"))
      (node (ref "IC4") (pin "39") (pinfunction "VSS_39") (pintype "passive"))
      (node (ref "IC4") (pin "6") (pinfunction "VSS_6") (pintype "passive"))
      (node (ref "IC5") (pin "16") (pinfunction "AVSS_16") (pintype "passive"))
      (node (ref "IC5") (pin "29") (pinfunction "VSS_29") (pintype "passive"))
      (node (ref "IC5") (pin "39") (pinfunction "VSS_39") (pintype "passive"))
      (node (ref "IC5") (pin "6") (pinfunction "VSS_6") (pintype "passive"))
      (node (ref "J1") (pin "1") (pinfunction "S_1") (pintype "passive"))
      (node (ref "R20") (pin "2") (pinfunction "2_2") (pintype "passive"))
      (node (ref "R24") (pin "2") (pinfunction "2_2") (pintype "passive"))
      (node (ref "R4") (pin "1") (pinfunction "1_1") (pintype "passive"))
      (node (ref "R5") (pin "1") (pinfunction "1_1") (pintype "passive"))
      (node (ref "R79") (pin "2") (pinfunction "2_2") (pintype "passive"))
      (node (ref "S1") (pin "3") (pinfunction "P_3") (pintype "passive"))
      (node (ref "S1") (pin "4") (pinfunction "P1_4") (pintype "passive"))
      (node (ref "SV1") (pin "3") (pinfunction "3_3") (pintype "passive"))
      (node (ref "SV1") (pin "5") (pinfunction "5_5") (pintype "passive"))
      (node (ref "SV1") (pin "7") (pinfunction "7_7") (pintype "passive"))
    )
    (net (code "13") (name "GNDIO") (class "Default")
      (node (ref "C1") (pin "2") (pinfunction "2_2") (pintype "passive"))
      (node (ref "C10") (pin "-") (pinfunction "-_-") (pintype "passive"))
      (node (ref "C11") (pin "2") (pinfunction "2_2") (pintype "passive"))
      (node (ref "C2") (pin "-") (pinfunction "-_-") (pintype "passive"))
      (node (ref "J10") (pin "1") (pinfunction "S_1") (pintype "passive"))
      (node (ref "J11") (pin "1") (pinfunction "S_1") (pintype "passive"))
      (node (ref "J12") (pin "1") (pinfunction "S_1") (pintype "passive"))
      (node (ref "J13") (pin "1") (pinfunction "S_1") (pintype "passive"))
      (node (ref "J14") (pin "1") (pinfunction "S_1") (pintype "passive"))
      (node (ref "J15") (pin "1") (pinfunction "S_1") (pintype "passive"))
      (node (ref "J2") (pin "1") (pinfunction "S_1") (pintype "passive"))
      (node (ref "J3") (pin "1") (pinfunction "S_1") (pintype "passive"))
      (node (ref "J4") (pin "1") (pinfunction "S_1") (pintype "passive"))
      (node (ref "J5") (pin "1") (pinfunction "S_1") (pintype "passive"))
      (node (ref "J6") (pin "1") (pinfunction "S_1") (pintype "passive"))
      (node (ref "J7") (pin "1") (pinfunction "S_1") (pintype "passive"))
      (node (ref "J8") (pin "1") (pinfunction "S_1") (pintype "passive"))
      (node (ref "J9") (pin "1") (pinfunction "S_1") (pintype "passive"))
      (node (ref "R10") (pin "1") (pinfunction "1_1") (pintype "passive"))
      (node (ref "R13") (pin "2") (pinfunction "2_2") (pintype "passive"))
      (node (ref "R3") (pin "1") (pinfunction "1_1") (pintype "passive"))
      (node (ref "R35") (pin "1") (pinfunction "1_1") (pintype "passive"))
      (node (ref "R37") (pin "1") (pinfunction "1_1") (pintype "passive"))
      (node (ref "R39") (pin "1") (pinfunction "1_1") (pintype "passive"))
      (node (ref "R41") (pin "1") (pinfunction "1_1") (pintype "passive"))
      (node (ref "R43") (pin "1") (pinfunction "1_1") (pintype "passive"))
      (node (ref "R45") (pin "1") (pinfunction "1_1") (pintype "passive"))
      (node (ref "R47") (pin "1") (pinfunction "1_1") (pintype "passive"))
      (node (ref "R5") (pin "2") (pinfunction "2_2") (pintype "passive"))
      (node (ref "R6") (pin "2") (pinfunction "2_2") (pintype "passive"))
      (node (ref "R67") (pin "1") (pinfunction "1_1") (pintype "passive"))
      (node (ref "R7") (pin "2") (pinfunction "2_2") (pintype "passive"))
      (node (ref "SV1") (pin "10") (pinfunction "10_10") (pintype "passive"))
      (node (ref "SV1") (pin "2") (pinfunction "2_2") (pintype "passive"))
      (node (ref "X1") (pin "1") (pinfunction "KL_1") (pintype "passive"))
      (node (ref "X2") (pin "1") (pinfunction "KL_1") (pintype "passive"))
    )
    (net (code "14") (name "GND_SERVO_5V") (class "Default")
      (node (ref "J16") (pin "1") (pinfunction "S_1") (pintype "passive"))
      (node (ref "J17") (pin "1") (pinfunction "S_1") (pintype "passive"))
      (node (ref "J18") (pin "1") (pinfunction "S_1") (pintype "passive"))
      (node (ref "J19") (pin "1") (pinfunction "S_1") (pintype "passive"))
      (node (ref "J20") (pin "1") (pinfunction "S_1") (pintype "passive"))
      (node (ref "R6") (pin "1") (pinfunction "1_1") (pintype "passive"))
    )
    (net (code "15") (name "GND_SERVO_9.6V") (class "Default")
      (node (ref "C12") (pin "-") (pinfunction "-_-") (pintype "passive"))
      (node (ref "C13") (pin "2") (pinfunction "2_2") (pintype "passive"))
      (node (ref "J21") (pin "1") (pinfunction "S_1") (pintype "passive"))
      (node (ref "R11") (pin "1") (pinfunction "1_1") (pintype "passive"))
      (node (ref "R12") (pin "1") (pinfunction "1_1") (pintype "passive"))
      (node (ref "R13") (pin "1") (pinfunction "1_1") (pintype "passive"))
    )
    (net (code "16") (name "G_RST") (class "Default")
      (node (ref "CN1") (pin "1") (pinfunction "1_1") (pintype "passive"))
      (node (ref "IC4") (pin "18") (pinfunction "MCLR_18") (pintype "passive"))
      (node (ref "IC5") (pin "18") (pinfunction "MCLR_18") (pintype "passive"))
      (node (ref "R21") (pin "1") (pinfunction "1_1") (pintype "passive"))
      (node (ref "S1") (pin "1") (pinfunction "S_1") (pintype "passive"))
      (node (ref "S1") (pin "2") (pinfunction "S1_2") (pintype "passive"))
    )
    (net (code "17") (name "I2C_SCL_(5V)") (class "Default")
      (node (ref "IC4") (pin "42") (pinfunction "PGEC3/ASCL1/RP6*/CN24/PMD6/RB6_42") (pintype "passive"))
      (node (ref "IC5") (pin "42") (pinfunction "PGEC3/ASCL1/RP6*/CN24/PMD6/RB6_42") (pintype "passive"))
      (node (ref "R16") (pin "1") (pinfunction "1_1") (pintype "passive"))
      (node (ref "SV1") (pin "4") (pinfunction "4_4") (pintype "passive"))
    )
    (net (code "18") (name "I2C_SDA_(5V)") (class "Default")
      (node (ref "IC4") (pin "41") (pinfunction "PGED3/ASDA1/RP5*/CN27/PMD7/RB5_41") (pintype "passive"))
      (node (ref "IC5") (pin "41") (pinfunction "PGED3/ASDA1/RP5*/CN27/PMD7/RB5_41") (pintype "passive"))
      (node (ref "R17") (pin "1") (pinfunction "1_1") (pintype "passive"))
      (node (ref "SV1") (pin "6") (pinfunction "6_6") (pintype "passive"))
    )
    (net (code "19") (name "L_ENC_CHA") (class "Default")
      (node (ref "IC4") (pin "36") (pinfunction "RP19*/CN28/PMBE/RC3_36") (pintype "passive"))
      (node (ref "J13") (pin "3") (pinfunction "S_3") (pintype "passive"))
    )
    (net (code "20") (name "L_ENC_CHB") (class "Default")
      (node (ref "IC4") (pin "33") (pinfunction "SOSCI/RP4*/CN1/RB4_33") (pintype "passive"))
      (node (ref "J13") (pin "4") (pinfunction "S_4") (pintype "passive"))
    )
    (net (code "21") (name "L_MOT_BREAK") (class "Default")
      (node (ref "IC4") (pin "13") (pinfunction "TCK/PMA7/RA7_13") (pintype "passive"))
      (node (ref "J22") (pin "1") (pinfunction "S_1") (pintype "passive"))
    )
    (net (code "22") (name "L_MOT_CURRENT") (class "Default")
      (node (ref "IC15") (pin "7") (pinfunction "VIOUT_7") (pintype "output"))
      (node (ref "IC4") (pin "24") (pinfunction "AN5/C1IN+/RP3*/CN7/RB3_24") (pintype "passive"))
    )
    (net (code "23") (name "L_MOT_REV") (class "Default")
      (node (ref "IC4") (pin "12") (pinfunction "TMS/PMA10/RA10_12") (pintype "passive"))
      (node (ref "J22") (pin "2") (pinfunction "S_2") (pintype "passive"))
    )
    (net (code "24") (name "L_MOT_VREF") (class "Default")
      (node (ref "IC14") (pin "1") (pinfunction "OUT_1") (pintype "output"))
      (node (ref "J22") (pin "3") (pinfunction "S_3") (pintype "passive"))
      (node (ref "R70") (pin "2") (pinfunction "2_2") (pintype "passive"))
    )
    (net (code "25") (name "L_MOT_VREF_N") (class "Default")
      (node (ref "IC4") (pin "15") (pinfunction "PWM1L1/DAC1LN/RP15*/CN11/PMCS1/RB15_15") (pintype "passive"))
      (node (ref "R72") (pin "1") (pinfunction "1_1") (pintype "passive"))
    )
    (net (code "26") (name "L_MOT_VREF_P") (class "Default")
      (node (ref "IC4") (pin "14") (pinfunction "PWM1H1/DAC1LP/RTCC/RP14*/CN12/PMWR/RB14_14") (pintype "passive"))
      (node (ref "R74") (pin "1") (pinfunction "1_1") (pintype "passive"))
    )
    (net (code "27") (name "MAIN_LASER_1") (class "Default")
      (node (ref "IC4") (pin "26") (pinfunction "AN7/DAC1LM/RP17*/CN9/RC1_26") (pintype "passive"))
      (node (ref "IC6") (pin "1") (pinfunction "OUT_1") (pintype "output"))
      (node (ref "R25") (pin "2") (pinfunction "2_2") (pintype "passive"))
    )
    (net (code "28") (name "MAIN_LASER_2") (class "Default")
      (node (ref "IC4") (pin "25") (pinfunction "AN6/DAC1RM/RP16*/CN8/RC0_25") (pintype "passive"))
      (node (ref "IC6") (pin "7") (pinfunction "OUT_7") (pintype "output"))
      (node (ref "R30") (pin "2") (pinfunction "2_2") (pintype "passive"))
    )
    (net (code "29") (name "MAIN_LED1") (class "Default")
      (node (ref "IC4") (pin "34") (pinfunction "SOSCO/T1CK/CN0/RA4_34") (pintype "passive"))
      (node (ref "R18") (pin "1") (pinfunction "1_1") (pintype "passive"))
    )
    (net (code "30") (name "MAIN_LED2") (class "Default")
      (node (ref "IC4") (pin "32") (pinfunction "TDO/PMA8/RA8_32") (pintype "passive"))
      (node (ref "R19") (pin "1") (pinfunction "1_1") (pintype "passive"))
    )
    (net (code "31") (name "MAIN_LED3") (class "Default")
      (node (ref "IC4") (pin "27") (pinfunction "AN8/CVREF/RP18*/PMA2/CN10/RC2_27") (pintype "passive"))
      (node (ref "R15") (pin "1") (pinfunction "1_1") (pintype "passive"))
    )
    (net (code "32") (name "MAIN_LED4") (class "Default")
      (node (ref "IC4") (pin "4") (pinfunction "RP24*/CN20/PMA5/RC8_4") (pintype "passive"))
      (node (ref "R14") (pin "1") (pinfunction "1_1") (pintype "passive"))
    )
    (net (code "33") (name "MAIN_PGED") (class "Default")
      (node (ref "IC4") (pin "21") (pinfunction "PGED1/AN2/C2IN-/RP0*/CN4/RB0_21") (pintype "passive"))
      (node (ref "JP1") (pin "1") (pinfunction "1_1") (pintype "passive"))
    )
    (net (code "34") (name "MAIN_SERVO_PWM_1") (class "Default")
      (node (ref "IC4") (pin "2") (pinfunction "PWM2H1/RP22*/CN18/PMA1/RC6_2") (pintype "passive"))
      (node (ref "J17") (pin "3") (pinfunction "S_3") (pintype "passive"))
      (node (ref "R50") (pin "1") (pinfunction "1_1") (pintype "passive"))
    )
    (net (code "35") (name "MAIN_SERVO_PWM_2") (class "Default")
      (node (ref "IC4") (pin "3") (pinfunction "PWM2L1/RP23*/CN17/PMA0/RC7_3") (pintype "passive"))
      (node (ref "J19") (pin "3") (pinfunction "S_3") (pintype "passive"))
      (node (ref "R52") (pin "1") (pinfunction "1_1") (pintype "passive"))
    )
    (net (code "36") (name "MAIN_UART_RX") (class "Default")
      (node (ref "IC4") (pin "44") (pinfunction "SCL1/RP8*/CN22/PMD4/RB8_44") (pintype "passive"))
      (node (ref "JP2") (pin "1") (pinfunction "1_1") (pintype "passive"))
      (node (ref "JP3") (pin "2") (pinfunction "2_2") (pintype "passive"))
    )
    (net (code "37") (name "MAIN_UART_TX") (class "Default")
      (node (ref "IC4") (pin "43") (pinfunction "INT0/RP7*/CN23/PMD5/RB7_43") (pintype "passive"))
      (node (ref "JP2") (pin "2") (pinfunction "2_2") (pintype "passive"))
      (node (ref "JP3") (pin "1") (pinfunction "1_1") (pintype "passive"))
    )
    (net (code "38") (name "Net-(IC3-ADJ)") (class "Default")
      (node (ref "IC3") (pin "1") (pinfunction "ADJ_1") (pintype "input"))
      (node (ref "R12") (pin "2") (pinfunction "2_2") (pintype "passive"))
      (node (ref "R8") (pin "1") (pinfunction "1_1") (pintype "passive"))
    )
    (net (code "39") (name "Net-(IC3-IN)") (class "Default")
      (node (ref "C10") (pin "+") (pinfunction "+_+") (pintype "passive"))
      (node (ref "C11") (pin "1") (pinfunction "1_1") (pintype "passive"))
      (node (ref "F2") (pin "1") (pinfunction "1_1") (pintype "passive"))
      (node (ref "IC3") (pin "3") (pinfunction "IN_3") (pintype "input"))
      (node (ref "X2") (pin "2") (pinfunction "KL_2") (pintype "passive"))
    )
    (net (code "40") (name "Net-(IC4-OSC1{slash}CLKI{slash}CN30{slash}RA2)") (class "Default")
      (node (ref "C17") (pin "1") (pinfunction "1_1") (pintype "passive"))
      (node (ref "IC4") (pin "30") (pinfunction "OSC1/CLKI/CN30/RA2_30") (pintype "passive"))
      (node (ref "Q1") (pin "1") (pinfunction "1_1") (pintype "passive"))
    )
    (net (code "41") (name "Net-(IC4-OSC2{slash}CLKO{slash}CN29{slash}RA3)") (class "Default")
      (node (ref "C18") (pin "1") (pinfunction "1_1") (pintype "passive"))
      (node (ref "IC4") (pin "31") (pinfunction "OSC2/CLKO/CN29/RA3_31") (pintype "passive"))
      (node (ref "Q1") (pin "2") (pinfunction "2_2") (pintype "passive"))
    )
    (net (code "42") (name "Net-(IC4-VCAP{slash}VDDCORE)") (class "Default")
      (node (ref "C15") (pin "+") (pinfunction "+_+") (pintype "passive"))
      (node (ref "IC4") (pin "7") (pinfunction "VCAP/VDDCORE_7") (pintype "passive"))
    )
    (net (code "43") (name "Net-(IC5-OSC1{slash}CLKI{slash}CN30{slash}RA2)") (class "Default")
      (node (ref "C23") (pin "1") (pinfunction "1_1") (pintype "passive"))
      (node (ref "IC5") (pin "30") (pinfunction "OSC1/CLKI/CN30/RA2_30") (pintype "passive"))
      (node (ref "Q2") (pin "1") (pinfunction "1_1") (pintype "passive"))
    )
    (net (code "44") (name "Net-(IC5-OSC2{slash}CLKO{slash}CN29{slash}RA3)") (class "Default")
      (node (ref "C24") (pin "1") (pinfunction "1_1") (pintype "passive"))
      (node (ref "IC5") (pin "31") (pinfunction "OSC2/CLKO/CN29/RA3_31") (pintype "passive"))
      (node (ref "Q2") (pin "2") (pinfunction "2_2") (pintype "passive"))
    )
    (net (code "45") (name "Net-(IC5-VCAP{slash}VDDCORE)") (class "Default")
      (node (ref "C21") (pin "+") (pinfunction "+_+") (pintype "passive"))
      (node (ref "IC5") (pin "7") (pinfunction "VCAP/VDDCORE_7") (pintype "passive"))
    )
    (net (code "46") (name "Net-(IC6A-+IN)") (class "Default")
      (node (ref "C26") (pin "1") (pinfunction "1_1") (pintype "passive"))
      (node (ref "IC6") (pin "3") (pinfunction "+IN_3") (pintype "input"))
      (node (ref "R27") (pin "2") (pinfunction "2_2") (pintype "passive"))
      (node (ref "R28") (pin "2") (pinfunction "2_2") (pintype "passive"))
    )
    (net (code "47") (name "Net-(IC6A--IN)") (class "Default")
      (node (ref "IC6") (pin "2") (pinfunction "-IN_2") (pintype "input"))
      (node (ref "R25") (pin "1") (pinfunction "1_1") (pintype "passive"))
      (node (ref "R26") (pin "2") (pinfunction "2_2") (pintype "passive"))
    )
    (net (code "48") (name "Net-(IC6B-+IN)") (class "Default")
      (node (ref "C29") (pin "1") (pinfunction "1_1") (pintype "passive"))
      (node (ref "IC6") (pin "5") (pinfunction "+IN_5") (pintype "input"))
      (node (ref "R32") (pin "2") (pinfunction "2_2") (pintype "passive"))
      (node (ref "R33") (pin "2") (pinfunction "2_2") (pintype "passive"))
    )
    (net (code "49") (name "Net-(IC6B--IN)") (class "Default")
      (node (ref "IC6") (pin "6") (pinfunction "-IN_6") (pintype "input"))
      (node (ref "R30") (pin "1") (pinfunction "1_1") (pintype "passive"))
      (node (ref "R31") (pin "2") (pinfunction "2_2") (pintype "passive"))
    )
    (net (code "50") (name "Net-(IC7-OUTA)") (class "Default")
      (node (ref "IC7") (pin "7") (pinfunction "OUTA_7") (pintype "output"))
      (node (ref "R57") (pin "1") (pinfunction "1_1") (pintype "passive"))
    )
    (net (code "51") (name "Net-(IC7-OUTB)") (class "Default")
      (node (ref "IC7") (pin "5") (pinfunction "OUTB_5") (pintype "output"))
      (node (ref "R58") (pin "1") (pinfunction "1_1") (pintype "passive"))
    )
    (net (code "52") (name "Net-(IC8A-G)") (class "Default")
      (node (ref "IC8") (pin "2") (pinfunction "G_2") (pintype "bidirectional"))
      (node (ref "IC8") (pin "4") (pinfunction "G_4") (pintype "bidirectional"))
      (node (ref "R58") (pin "2") (pinfunction "2_2") (pintype "passive"))
      (node (ref "R60") (pin "2") (pinfunction "2_2") (pintype "passive"))
    )
    (net (code "53") (name "Net-(IC9A-G)") (class "Default")
      (node (ref "IC9") (pin "2") (pinfunction "G_2") (pintype "bidirectional"))
      (node (ref "IC9") (pin "4") (pinfunction "G_4") (pintype "bidirectional"))
      (node (ref "R57") (pin "2") (pinfunction "2_2") (pintype "passive"))
      (node (ref "R59") (pin "2") (pinfunction "2_2") (pintype "passive"))
    )
    (net (code "54") (name "Net-(IC10-OUTA)") (class "Default")
      (node (ref "D1") (pin "A") (pinfunction "A_A") (pintype "passive"))
      (node (ref "IC10") (pin "7") (pinfunction "OUTA_7") (pintype "output"))
      (node (ref "K1") (pin "2") (pinfunction "2_2") (pintype "passive"))
    )
    (net (code "55") (name "Net-(IC10-OUTB)") (class "Default")
      (node (ref "D2") (pin "A") (pinfunction "A_A") (pintype "passive"))
      (node (ref "IC10") (pin "5") (pinfunction "OUTB_5") (pintype "output"))
      (node (ref "X7") (pin "1") (pinfunction "KL_1") (pintype "passive"))
    )
    (net (code "56") (name "Net-(IC11-OUTA)") (class "Default")
      (node (ref "IC11") (pin "7") (pinfunction "OUTA_7") (pintype "output"))
      (node (ref "R65") (pin "1") (pinfunction "1_1") (pintype "passive"))
    )
    (net (code "57") (name "Net-(IC11-OUTB)") (class "Default")
      (node (ref "IC11") (pin "5") (pinfunction "OUTB_5") (pintype "output"))
      (node (ref "R66") (pin "1") (pinfunction "1_1") (pintype "passive"))
    )
    (net (code "58") (name "Net-(IC12A-G)") (class "Default")
      (node (ref "IC12") (pin "2") (pinfunction "G_2") (pintype "bidirectional"))
      (node (ref "IC12") (pin "4") (pinfunction "G_4") (pintype "bidirectional"))
      (node (ref "R66") (pin "2") (pinfunction "2_2") (pintype "passive"))
      (node (ref "R69") (pin "2") (pinfunction "2_2") (pintype "passive"))
    )
    (net (code "59") (name "Net-(IC13A-G)") (class "Default")
      (node (ref "IC13") (pin "2") (pinfunction "G_2") (pintype "bidirectional"))
      (node (ref "IC13") (pin "4") (pinfunction "G_4") (pintype "bidirectional"))
      (node (ref "R65") (pin "2") (pinfunction "2_2") (pintype "passive"))
      (node (ref "R68") (pin "2") (pinfunction "2_2") (pintype "passive"))
    )
    (net (code "60") (name "Net-(IC14A-+IN)") (class "Default")
      (node (ref "IC14") (pin "3") (pinfunction "+IN_3") (pintype "input"))
      (node (ref "R74") (pin "2") (pinfunction "2_2") (pintype "passive"))
      (node (ref "R76") (pin "2") (pinfunction "2_2") (pintype "passive"))
    )
    (net (code "61") (name "Net-(IC14A--IN)") (class "Default")
      (node (ref "IC14") (pin "2") (pinfunction "-IN_2") (pintype "input"))
      (node (ref "R70") (pin "1") (pinfunction "1_1") (pintype "passive"))
      (node (ref "R72") (pin "2") (pinfunction "2_2") (pintype "passive"))
    )
    (net (code "62") (name "Net-(IC14B-+IN)") (class "Default")
      (node (ref "IC14") (pin "5") (pinfunction "+IN_5") (pintype "input"))
      (node (ref "R75") (pin "2") (pinfunction "2_2") (pintype "passive"))
      (node (ref "R77") (pin "2") (pinfunction "2_2") (pintype "passive"))
    )
    (net (code "63") (name "Net-(IC14B--IN)") (class "Default")
      (node (ref "IC14") (pin "6") (pinfunction "-IN_6") (pintype "input"))
      (node (ref "R71") (pin "1") (pinfunction "1_1") (pintype "passive"))
      (node (ref "R73") (pin "2") (pinfunction "2_2") (pintype "passive"))
    )
    (net (code "64") (name "Net-(IC15-FILTER)") (class "Default")
      (node (ref "C36") (pin "2") (pinfunction "2_2") (pintype "passive"))
      (node (ref "IC15") (pin "6") (pinfunction "FILTER_6") (pintype "passive"))
    )
    (net (code "65") (name "Net-(IC16-FILTER)") (class "Default")
      (node (ref "C38") (pin "2") (pinfunction "2_2") (pintype "passive"))
      (node (ref "IC16") (pin "6") (pinfunction "FILTER_6") (pintype "passive"))
    )
    (net (code "66") (name "Net-(IC17A-+IN)") (class "Default")
      (node (ref "IC17") (pin "3") (pinfunction "+IN_3") (pintype "input"))
      (node (ref "R83") (pin "2") (pinfunction "2_2") (pintype "passive"))
      (node (ref "R84") (pin "2") (pinfunction "2_2") (pintype "passive"))
    )
    (net (code "67") (name "Net-(IC17A--IN)") (class "Default")
      (node (ref "IC17") (pin "2") (pinfunction "-IN_2") (pintype "input"))
      (node (ref "R80") (pin "1") (pinfunction "1_1") (pintype "passive"))
      (node (ref "R82") (pin "2") (pinfunction "2_2") (pintype "passive"))
    )
    (net (code "68") (name "Net-(IC17B-+IN)") (class "Default")
      (node (ref "IC17") (pin "5") (pinfunction "+IN_5") (pintype "input"))
      (node (ref "R81") (pin "1") (pinfunction "1_1") (pintype "passive"))
      (node (ref "R85") (pin "2") (pinfunction "2_2") (pintype "passive"))
    )
    (net (code "69") (name "Net-(IC18-FILTER)") (class "Default")
      (node (ref "C42") (pin "2") (pinfunction "2_2") (pintype "passive"))
      (node (ref "IC18") (pin "6") (pinfunction "FILTER_6") (pintype "passive"))
    )
    (net (code "70") (name "Net-(IC19-NCTS)") (class "Default")
      (node (ref "IC19") (pin "10") (pinfunction "NCTS_10") (pintype "passive"))
      (node (ref "IC19") (pin "5") (pinfunction "NRTS_5") (pintype "passive"))
    )
    (net (code "71") (name "Net-(IC20-NCTS)") (class "Default")
      (node (ref "IC20") (pin "10") (pinfunction "NCTS_10") (pintype "passive"))
      (node (ref "IC20") (pin "5") (pinfunction "NRTS_5") (pintype "passive"))
    )
    (net (code "72") (name "Net-(IC21A-C1+)") (class "Default")
      (node (ref "C43") (pin "2") (pinfunction "2_2") (pintype "passive"))
      (node (ref "IC21") (pin "1") (pinfunction "C1+_1") (pintype "bidirectional"))
    )
    (net (code "73") (name "Net-(IC21A-C1-)") (class "Default")
      (node (ref "C43") (pin "1") (pinfunction "1_1") (pintype "passive"))
      (node (ref "IC21") (pin "3") (pinfunction "C1-_3") (pintype "bidirectional"))
    )
    (net (code "74") (name "Net-(IC21A-C2+)") (class "Default")
      (node (ref "C46") (pin "2") (pinfunction "2_2") (pintype "passive"))
      (node (ref "IC21") (pin "4") (pinfunction "C2+_4") (pintype "bidirectional"))
    )
    (net (code "75") (name "Net-(IC21A-C2-)") (class "Default")
      (node (ref "C46") (pin "1") (pinfunction "1_1") (pintype "passive"))
      (node (ref "IC21") (pin "5") (pinfunction "C2-_5") (pintype "bidirectional"))
    )
    (net (code "76") (name "Net-(IC21A-V+)") (class "Default")
      (node (ref "C44") (pin "1") (pinfunction "1_1") (pintype "passive"))
      (node (ref "IC21") (pin "2") (pinfunction "V+_2") (pintype "bidirectional"))
    )
    (net (code "77") (name "Net-(IC21A-V-)") (class "Default")
      (node (ref "C47") (pin "2") (pinfunction "2_2") (pintype "passive"))
      (node (ref "IC21") (pin "6") (pinfunction "V-_6") (pintype "bidirectional"))
    )
    (net (code "78") (name "Net-(J2C-S)") (class "Default")
      (node (ref "J2") (pin "3") (pinfunction "S_3") (pintype "passive"))
      (node (ref "R27") (pin "1") (pinfunction "1_1") (pintype "passive"))
    )
    (net (code "79") (name "Net-(J2E-S)") (class "Default")
      (node (ref "J2") (pin "5") (pinfunction "S_5") (pintype "passive"))
      (node (ref "J3") (pin "2") (pinfunction "S_2") (pintype "passive"))
      (node (ref "R29") (pin "1") (pinfunction "1_1") (pintype "passive"))
    )
    (net (code "80") (name "Net-(J4C-S)") (class "Default")
      (node (ref "J4") (pin "3") (pinfunction "S_3") (pintype "passive"))
      (node (ref "R32") (pin "1") (pinfunction "1_1") (pintype "passive"))
    )
    (net (code "81") (name "Net-(J4E-S)") (class "Default")
      (node (ref "J4") (pin "5") (pinfunction "S_5") (pintype "passive"))
      (node (ref "J5") (pin "2") (pinfunction "S_2") (pintype "passive"))
      (node (ref "R34") (pin "1") (pinfunction "1_1") (pintype "passive"))
    )
    (net (code "82") (name "Net-(LED1-PadC)") (class "Default")
      (node (ref "LED1") (pin "C") (pinfunction "C_C") (pintype "passive"))
      (node (ref "R3") (pin "2") (pinfunction "2_2") (pintype "passive"))
    )
    (net (code "83") (name "Net-(LED2-PadC)") (class "Default")
      (node (ref "LED2") (pin "C") (pinfunction "C_C") (pintype "passive"))
      (node (ref "R4") (pin "2") (pinfunction "2_2") (pintype "passive"))
    )
    (net (code "84") (name "Net-(LED3-PadC)") (class "Default")
      (node (ref "LED3") (pin "C") (pinfunction "C_C") (pintype "passive"))
      (node (ref "R9") (pin "2") (pinfunction "2_2") (pintype "passive"))
    )
    (net (code "85") (name "Net-(LED4-PadC)") (class "Default")
      (node (ref "LED4") (pin "C") (pinfunction "C_C") (pintype "passive"))
      (node (ref "R10") (pin "2") (pinfunction "2_2") (pintype "passive"))
    )
    (net (code "86") (name "Net-(LED5-PadC)") (class "Default")
      (node (ref "LED5") (pin "C") (pinfunction "C_C") (pintype "passive"))
      (node (ref "R11") (pin "2") (pinfunction "2_2") (pintype "passive"))
    )
    (net (code "87") (name "Net-(LED6-PadC)") (class "Default")
      (node (ref "LED6") (pin "C") (pinfunction "C_C") (pintype "passive"))
      (node (ref "R14") (pin "2") (pinfunction "2_2") (pintype "passive"))
    )
    (net (code "88") (name "Net-(LED7-PadC)") (class "Default")
      (node (ref "LED7") (pin "C") (pinfunction "C_C") (pintype "passive"))
      (node (ref "R15") (pin "2") (pinfunction "2_2") (pintype "passive"))
    )
    (net (code "89") (name "Net-(LED8-PadC)") (class "Default")
      (node (ref "LED8") (pin "C") (pinfunction "C_C") (pintype "passive"))
      (node (ref "R18") (pin "2") (pinfunction "2_2") (pintype "passive"))
    )
    (net (code "90") (name "Net-(LED9-PadC)") (class "Default")
      (node (ref "LED9") (pin "C") (pinfunction "C_C") (pintype "passive"))
      (node (ref "R19") (pin "2") (pinfunction "2_2") (pintype "passive"))
    )
    (net (code "91") (name "Net-(LED10-PadC)") (class "Default")
      (node (ref "LED10") (pin "C") (pinfunction "C_C") (pintype "passive"))
      (node (ref "R23") (pin "2") (pinfunction "2_2") (pintype "passive"))
    )
    (net (code "92") (name "Net-(X1B-KL)") (class "Default")
      (node (ref "F1") (pin "1") (pinfunction "1_1") (pintype "passive"))
      (node (ref "R1") (pin "2") (pinfunction "2_2") (pintype "passive"))
      (node (ref "X1") (pin "2") (pinfunction "KL_2") (pintype "passive"))
    )
    (net (code "93") (name "Net-(X4A-KL)") (class "Default")
      (node (ref "IC9") (pin "5") (pinfunction "D_5") (pintype "bidirectional"))
      (node (ref "IC9") (pin "6") (pinfunction "D_6") (pintype "bidirectional"))
      (node (ref "IC9") (pin "7") (pinfunction "D_7") (pintype "bidirectional"))
      (node (ref "IC9") (pin "8") (pinfunction "D_8") (pintype "bidirectional"))
      (node (ref "X4") (pin "1") (pinfunction "KL_1") (pintype "passive"))
    )
    (net (code "94") (name "Net-(X4B-KL)") (class "Default")
      (node (ref "IC8") (pin "5") (pinfunction "D_5") (pintype "bidirectional"))
      (node (ref "IC8") (pin "6") (pinfunction "D_6") (pintype "bidirectional"))
      (node (ref "IC8") (pin "7") (pinfunction "D_7") (pintype "bidirectional"))
      (node (ref "IC8") (pin "8") (pinfunction "D_8") (pintype "bidirectional"))
      (node (ref "X4") (pin "2") (pinfunction "KL_2") (pintype "passive"))
    )
    (net (code "95") (name "Net-(X5A-KL)") (class "Default")
      (node (ref "X5") (pin "1") (pinfunction "KL_1") (pintype "passive"))
      (node (ref "X6") (pin "1") (pinfunction "KL_1") (pintype "passive"))
    )
    (net (code "96") (name "Net-(X5B-KL)") (class "Default")
      (node (ref "K1") (pin "P") (pinfunction "P_P") (pintype "passive"))
      (node (ref "X5") (pin "2") (pinfunction "KL_2") (pintype "passive"))
    )
    (net (code "97") (name "Net-(X6B-KL)") (class "Default")
      (node (ref "K1") (pin "S") (pinfunction "S_S") (pintype "passive"))
      (node (ref "X6") (pin "2") (pinfunction "KL_2") (pintype "passive"))
    )
    (net (code "98") (name "Net-(X8A-KL)") (class "Default")
      (node (ref "IC13") (pin "5") (pinfunction "D_5") (pintype "bidirectional"))
      (node (ref "IC13") (pin "6") (pinfunction "D_6") (pintype "bidirectional"))
      (node (ref "IC13") (pin "7") (pinfunction "D_7") (pintype "bidirectional"))
      (node (ref "IC13") (pin "8") (pinfunction "D_8") (pintype "bidirectional"))
      (node (ref "X8") (pin "1") (pinfunction "KL_1") (pintype "passive"))
    )
    (net (code "99") (name "Net-(X8B-KL)") (class "Default")
      (node (ref "IC12") (pin "5") (pinfunction "D_5") (pintype "bidirectional"))
      (node (ref "IC12") (pin "6") (pinfunction "D_6") (pintype "bidirectional"))
      (node (ref "IC12") (pin "7") (pinfunction "D_7") (pintype "bidirectional"))
      (node (ref "IC12") (pin "8") (pinfunction "D_8") (pintype "bidirectional"))
      (node (ref "X8") (pin "2") (pinfunction "KL_2") (pintype "passive"))
    )
    (net (code "100") (name "Net-(X9A-KL)") (class "Default")
      (node (ref "IC15") (pin "1") (pinfunction "IP+_1") (pintype "passive"))
      (node (ref "IC15") (pin "2") (pinfunction "IP+_2") (pintype "passive"))
      (node (ref "X9") (pin "1") (pinfunction "KL_1") (pintype "passive"))
    )
    (net (code "101") (name "Net-(X10A-KL)") (class "Default")
      (node (ref "IC16") (pin "1") (pinfunction "IP+_1") (pintype "passive"))
      (node (ref "IC16") (pin "2") (pinfunction "IP+_2") (pintype "passive"))
      (node (ref "X10") (pin "1") (pinfunction "KL_1") (pintype "passive"))
    )
    (net (code "102") (name "Net-(X11A-KL)") (class "Default")
      (node (ref "IC18") (pin "1") (pinfunction "IP+_1") (pintype "passive"))
      (node (ref "IC18") (pin "2") (pinfunction "IP+_2") (pintype "passive"))
      (node (ref "X11") (pin "1") (pinfunction "KL_1") (pintype "passive"))
    )
    (net (code "103") (name "PGEC") (class "Default")
      (node (ref "CN1") (pin "5") (pinfunction "5_5") (pintype "passive"))
      (node (ref "IC4") (pin "22") (pinfunction "PGEC1/AN3/C2IN+/RP1*/CN5/RB1_22") (pintype "passive"))
      (node (ref "IC5") (pin "22") (pinfunction "PGEC1/AN3/C2IN+/RP1*/CN5/RB1_22") (pintype "passive"))
    )
    (net (code "104") (name "PGED") (class "Default")
      (node (ref "CN1") (pin "4") (pinfunction "4_4") (pintype "passive"))
      (node (ref "JP1") (pin "2") (pinfunction "2_2") (pintype "passive"))
    )
    (net (code "105") (name "RX_MAX232") (class "Default")
      (node (ref "IC21") (pin "12") (pinfunction "R1OUT_12") (pintype "output"))
      (node (ref "JP3") (pin "4") (pinfunction "4_4") (pintype "passive"))
    )
    (net (code "106") (name "RX_WT11") (class "Default")
      (node (ref "IC19") (pin "6") (pinfunction "RXD_6") (pintype "passive"))
      (node (ref "JP2") (pin "4") (pinfunction "4_4") (pintype "passive"))
    )
    (net (code "107") (name "R_ENC_CHA") (class "Default")
      (node (ref "IC4") (pin "38") (pinfunction "RP21*/CN26/PMA3/RC5_38") (pintype "passive"))
      (node (ref "J12") (pin "3") (pinfunction "S_3") (pintype "passive"))
    )
    (net (code "108") (name "R_ENC_CHB") (class "Default")
      (node (ref "IC4") (pin "37") (pinfunction "RP20*/CN25/PMA4/RC4_37") (pintype "passive"))
      (node (ref "J12") (pin "4") (pinfunction "S_4") (pintype "passive"))
    )
    (net (code "109") (name "R_MOT_BREAK") (class "Default")
      (node (ref "IC4") (pin "9") (pinfunction "PGEC2/PWM1L3/RP11*/CN15/PMD1/RB11_9") (pintype "passive"))
      (node (ref "J23") (pin "1") (pinfunction "S_1") (pintype "passive"))
    )
    (net (code "110") (name "R_MOT_CURRENT") (class "Default")
      (node (ref "IC16") (pin "7") (pinfunction "VIOUT_7") (pintype "output"))
      (node (ref "IC4") (pin "23") (pinfunction "AN4/C1IN-/RP2*/CN6/RB2_23") (pintype "passive"))
    )
    (net (code "111") (name "R_MOT_REV") (class "Default")
      (node (ref "IC4") (pin "8") (pinfunction "PGED2/EMCD2/PWM1H3/RP10*/CN16/PMD2/RB10_8") (pintype "passive"))
      (node (ref "J23") (pin "2") (pinfunction "S_2") (pintype "passive"))
    )
    (net (code "112") (name "R_MOT_VREF") (class "Default")
      (node (ref "IC14") (pin "7") (pinfunction "OUT_7") (pintype "output"))
      (node (ref "J23") (pin "3") (pinfunction "S_3") (pintype "passive"))
      (node (ref "R71") (pin "2") (pinfunction "2_2") (pintype "passive"))
    )
    (net (code "113") (name "R_MOT_VREF_N") (class "Default")
      (node (ref "IC4") (pin "11") (pinfunction "PWM1L2/DAC1RN/RP13*/CN13/PMRD/RB13_11") (pintype "passive"))
      (node (ref "R73") (pin "1") (pinfunction "1_1") (pintype "passive"))
    )
    (net (code "114") (name "R_MOT_VREF_P") (class "Default")
      (node (ref "IC4") (pin "10") (pinfunction "PWM1H2/DAC1RP/RP12*/CN14/PMD0/RB12_10") (pintype "passive"))
      (node (ref "R75") (pin "1") (pinfunction "1_1") (pintype "passive"))
    )
    (net (code "115") (name "SLAVE_BMOT_BREAK") (class "Default")
      (node (ref "IC5") (pin "13") (pinfunction "TCK/PMA7/RA7_13") (pintype "passive"))
      (node (ref "J24") (pin "1") (pinfunction "S_1") (pintype "passive"))
    )
    (net (code "116") (name "SLAVE_BMOT_CURRENT") (class "Default")
      (node (ref "IC18") (pin "7") (pinfunction "VIOUT_7") (pintype "output"))
      (node (ref "IC5") (pin "23") (pinfunction "AN4/C1IN-/RP2*/CN6/RB2_23") (pintype "passive"))
    )
    (net (code "117") (name "SLAVE_BMOT_REV") (class "Default")
      (node (ref "IC5") (pin "12") (pinfunction "TMS/PMA10/RA10_12") (pintype "passive"))
      (node (ref "J24") (pin "2") (pinfunction "S_2") (pintype "passive"))
    )
    (net (code "118") (name "SLAVE_BMOT_VREF") (class "Default")
      (node (ref "IC17") (pin "1") (pinfunction "OUT_1") (pintype "output"))
      (node (ref "J24") (pin "3") (pinfunction "S_3") (pintype "passive"))
      (node (ref "R80") (pin "2") (pinfunction "2_2") (pintype "passive"))
    )
    (net (code "119") (name "SLAVE_BMOT_VREF_N") (class "Default")
      (node (ref "IC5") (pin "15") (pinfunction "PWM1L1/DAC1LN/RP15*/CN11/PMCS1/RB15_15") (pintype "passive"))
      (node (ref "R82") (pin "1") (pinfunction "1_1") (pintype "passive"))
    )
    (net (code "120") (name "SLAVE_BMOT_VREF_P") (class "Default")
      (node (ref "IC5") (pin "14") (pinfunction "PWM1H1/DAC1LP/RTCC/RP14*/CN12/PMWR/RB14_14") (pintype "passive"))
      (node (ref "R83") (pin "1") (pinfunction "1_1") (pintype "passive"))
    )
    (net (code "121") (name "SLAVE_DRIVER_OUT") (class "Default")
      (node (ref "IC10") (pin "4") (pinfunction "INB_4") (pintype "input"))
      (node (ref "IC5") (pin "34") (pinfunction "SOSCO/T1CK/CN0/RA4_34") (pintype "passive"))
      (node (ref "R62") (pin "1") (pinfunction "1_1") (pintype "passive"))
    )
    (net (code "122") (name "SLAVE_ENC_CHA") (class "Default")
      (node (ref "IC5") (pin "38") (pinfunction "RP21*/CN26/PMA3/RC5_38") (pintype "passive"))
      (node (ref "J14") (pin "3") (pinfunction "S_3") (pintype "passive"))
    )
    (net (code "123") (name "SLAVE_ENC_CHB") (class "Default")
      (node (ref "IC5") (pin "37") (pinfunction "RP20*/CN25/PMA4/RC4_37") (pintype "passive"))
      (node (ref "J14") (pin "4") (pinfunction "S_4") (pintype "passive"))
    )
    (net (code "124") (name "SLAVE_LED1") (class "Default")
      (node (ref "IC5") (pin "5") (pinfunction "RP25*/CN19/PMA6/RC9_5") (pintype "passive"))
      (node (ref "R23") (pin "1") (pinfunction "1_1") (pintype "passive"))
    )
    (net (code "125") (name "SLAVE_MOT_1_INA") (class "Default")
      (node (ref "IC5") (pin "2") (pinfunction "PWM2H1/RP22*/CN18/PMA1/RC6_2") (pintype "passive"))
      (node (ref "IC7") (pin "2") (pinfunction "INA_2") (pintype "input"))
      (node (ref "R55") (pin "1") (pinfunction "1_1") (pintype "passive"))
    )
    (net (code "126") (name "SLAVE_MOT_1_INB") (class "Default")
      (node (ref "IC5") (pin "3") (pinfunction "PWM2L1/RP23*/CN17/PMA0/RC7_3") (pintype "passive"))
      (node (ref "IC7") (pin "4") (pinfunction "INB_4") (pintype "input"))
      (node (ref "R56") (pin "1") (pinfunction "1_1") (pintype "passive"))
    )
    (net (code "127") (name "SLAVE_MOT_2_INA") (class "Default")
      (node (ref "IC11") (pin "2") (pinfunction "INA_2") (pintype "input"))
      (node (ref "IC5") (pin "10") (pinfunction "PWM1H2/DAC1RP/RP12*/CN14/PMD0/RB12_10") (pintype "passive"))
      (node (ref "R63") (pin "1") (pinfunction "1_1") (pintype "passive"))
    )
    (net (code "128") (name "SLAVE_MOT_2_INB") (class "Default")
      (node (ref "IC11") (pin "4") (pinfunction "INB_4") (pintype "input"))
      (node (ref "IC5") (pin "11") (pinfunction "PWM1L2/DAC1RN/RP13*/CN13/PMRD/RB13_11") (pintype "passive"))
      (node (ref "R64") (pin "1") (pinfunction "1_1") (pintype "passive"))
    )
    (net (code "129") (name "SLAVE_PGED") (class "Default")
      (node (ref "IC5") (pin "21") (pinfunction "PGED1/AN2/C2IN-/RP0*/CN4/RB0_21") (pintype "passive"))
      (node (ref "JP1") (pin "3") (pinfunction "3_3") (pintype "passive"))
    )
    (net (code "130") (name "SLAVE_RELE_OUT") (class "Default")
      (node (ref "IC10") (pin "2") (pinfunction "INA_2") (pintype "input"))
      (node (ref "IC5") (pin "35") (pinfunction "TDI/PMA9/RA9_35") (pintype "passive"))
      (node (ref "R61") (pin "1") (pinfunction "1_1") (pintype "passive"))
    )
    (net (code "131") (name "SLAVE_SENSOR_1") (class "Default")
      (node (ref "IC5") (pin "9") (pinfunction "PGEC2/PWM1L3/RP11*/CN15/PMD1/RB11_9") (pintype "passive"))
      (node (ref "J6") (pin "3") (pinfunction "S_3") (pintype "passive"))
      (node (ref "R35") (pin "2") (pinfunction "2_2") (pintype "passive"))
      (node (ref "R36") (pin "1") (pinfunction "1_1") (pintype "passive"))
    )
    (net (code "132") (name "SLAVE_SENSOR_2") (class "Default")
      (node (ref "IC5") (pin "8") (pinfunction "PGED2/EMCD2/PWM1H3/RP10*/CN16/PMD2/RB10_8") (pintype "passive"))
      (node (ref "J7") (pin "3") (pinfunction "S_3") (pintype "passive"))
      (node (ref "R37") (pin "2") (pinfunction "2_2") (pintype "passive"))
      (node (ref "R38") (pin "1") (pinfunction "1_1") (pintype "passive"))
    )
    (net (code "133") (name "SLAVE_SENSOR_3") (class "Default")
      (node (ref "IC5") (pin "4") (pinfunction "RP24*/CN20/PMA5/RC8_4") (pintype "passive"))
      (node (ref "J8") (pin "3") (pinfunction "S_3") (pintype "passive"))
      (node (ref "R39") (pin "2") (pinfunction "2_2") (pintype "passive"))
      (node (ref "R40") (pin "1") (pinfunction "1_1") (pintype "passive"))
    )
    (net (code "134") (name "SLAVE_SENSOR_4") (class "Default")
      (node (ref "IC5") (pin "32") (pinfunction "TDO/PMA8/RA8_32") (pintype "passive"))
      (node (ref "J9") (pin "3") (pinfunction "S_3") (pintype "passive"))
      (node (ref "R41") (pin "2") (pinfunction "2_2") (pintype "passive"))
      (node (ref "R42") (pin "1") (pinfunction "1_1") (pintype "passive"))
    )
    (net (code "135") (name "SLAVE_SENSOR_5") (class "Default")
      (node (ref "IC5") (pin "36") (pinfunction "RP19*/CN28/PMBE/RC3_36") (pintype "passive"))
      (node (ref "J10") (pin "3") (pinfunction "S_3") (pintype "passive"))
      (node (ref "R43") (pin "2") (pinfunction "2_2") (pintype "passive"))
      (node (ref "R44") (pin "1") (pinfunction "1_1") (pintype "passive"))
    )
    (net (code "136") (name "SLAVE_SENSOR_6") (class "Default")
      (node (ref "IC5") (pin "33") (pinfunction "SOSCI/RP4*/CN1/RB4_33") (pintype "passive"))
      (node (ref "J11") (pin "3") (pinfunction "S_3") (pintype "passive"))
      (node (ref "R45") (pin "2") (pinfunction "2_2") (pintype "passive"))
      (node (ref "R46") (pin "1") (pinfunction "1_1") (pintype "passive"))
    )
    (net (code "137") (name "SLAVE_SENSOR_7") (class "Default")
      (node (ref "IC5") (pin "27") (pinfunction "AN8/CVREF/RP18*/PMA2/CN10/RC2_27") (pintype "passive"))
      (node (ref "J15") (pin "3") (pinfunction "S_3") (pintype "passive"))
      (node (ref "R47") (pin "2") (pinfunction "2_2") (pintype "passive"))
      (node (ref "R48") (pin "1") (pinfunction "1_1") (pintype "passive"))
    )
    (net (code "138") (name "SLAVE_SERVO_AX12") (class "Default")
      (node (ref "IC5") (pin "1") (pinfunction "SDA1/RP9*/CN21/PMD3/RB9_1") (pintype "passive"))
      (node (ref "J21") (pin "3") (pinfunction "S_3") (pintype "passive"))
      (node (ref "R54") (pin "1") (pinfunction "1_1") (pintype "passive"))
    )
    (net (code "139") (name "SLAVE_SERVO_PWM_1") (class "Default")
      (node (ref "IC5") (pin "24") (pinfunction "AN5/C1IN+/RP3*/CN7/RB3_24") (pintype "passive"))
      (node (ref "J16") (pin "3") (pinfunction "S_3") (pintype "passive"))
      (node (ref "R49") (pin "1") (pinfunction "1_1") (pintype "passive"))
    )
    (net (code "140") (name "SLAVE_SERVO_PWM_2") (class "Default")
      (node (ref "IC5") (pin "25") (pinfunction "AN6/DAC1RM/RP16*/CN8/RC0_25") (pintype "passive"))
      (node (ref "J18") (pin "3") (pinfunction "S_3") (pintype "passive"))
      (node (ref "R51") (pin "1") (pinfunction "1_1") (pintype "passive"))
    )
    (net (code "141") (name "SLAVE_SERVO_PWM_3") (class "Default")
      (node (ref "IC5") (pin "26") (pinfunction "AN7/DAC1LM/RP17*/CN9/RC1_26") (pintype "passive"))
      (node (ref "J20") (pin "3") (pinfunction "S_3") (pintype "passive"))
      (node (ref "R53") (pin "1") (pinfunction "1_1") (pintype "passive"))
    )
    (net (code "142") (name "SLAVE_UART_RX") (class "Default")
      (node (ref "IC5") (pin "44") (pinfunction "SCL1/RP8*/CN22/PMD4/RB8_44") (pintype "passive"))
      (node (ref "JP2") (pin "5") (pinfunction "5_5") (pintype "passive"))
      (node (ref "JP3") (pin "6") (pinfunction "6_6") (pintype "passive"))
    )
    (net (code "143") (name "SLAVE_UART_TX") (class "Default")
      (node (ref "IC5") (pin "43") (pinfunction "INT0/RP7*/CN23/PMD5/RB7_43") (pintype "passive"))
      (node (ref "JP2") (pin "6") (pinfunction "6_6") (pintype "passive"))
      (node (ref "JP3") (pin "5") (pinfunction "5_5") (pintype "passive"))
    )
    (net (code "144") (name "START") (class "Default")
      (node (ref "IC4") (pin "35") (pinfunction "TDI/PMA9/RA9_35") (pintype "passive"))
      (node (ref "J1") (pin "3") (pinfunction "S_3") (pintype "passive"))
      (node (ref "R22") (pin "1") (pinfunction "1_1") (pintype "passive"))
    )
    (net (code "145") (name "TO_RX_RS232_M") (class "Default")
      (node (ref "CON1") (pin "2") (pinfunction "2_2") (pintype "passive"))
      (node (ref "IC21") (pin "14") (pinfunction "T1OUT_14") (pintype "output"))
    )
    (net (code "146") (name "TX_MAX232") (class "Default")
      (node (ref "IC21") (pin "11") (pinfunction "T1IN_11") (pintype "input"))
      (node (ref "JP3") (pin "3") (pinfunction "3_3") (pintype "passive"))
    )
    (net (code "147") (name "TX_WT11") (class "Default")
      (node (ref "IC19") (pin "26") (pinfunction "TXD_26") (pintype "passive"))
      (node (ref "JP2") (pin "3") (pinfunction "3_3") (pintype "passive"))
    )
    (net (code "148") (name "VCC_SERVO_5V") (class "Default")
      (node (ref "J16") (pin "2") (pinfunction "S_2") (pintype "passive"))
      (node (ref "J17") (pin "2") (pinfunction "S_2") (pintype "passive"))
      (node (ref "J18") (pin "2") (pinfunction "S_2") (pintype "passive"))
      (node (ref "J19") (pin "2") (pinfunction "S_2") (pintype "passive"))
      (node (ref "J20") (pin "2") (pinfunction "S_2") (pintype "passive"))
      (node (ref "R1") (pin "1") (pinfunction "1_1") (pintype "passive"))
    )
    (net (code "149") (name "VCC_SERVO_9.6V") (class "Default")
      (node (ref "C12") (pin "+") (pinfunction "+_+") (pintype "passive"))
      (node (ref "C13") (pin "1") (pinfunction "1_1") (pintype "passive"))
      (node (ref "IC3") (pin "2") (pinfunction "OUT_2") (pintype "passive"))
      (node (ref "J21") (pin "2") (pinfunction "S_2") (pintype "passive"))
      (node (ref "LED5") (pin "A") (pinfunction "A_A") (pintype "passive"))
      (node (ref "R8") (pin "2") (pinfunction "2_2") (pintype "passive"))
    )
    (net (code "150") (name "VOFF_2V") (class "Default")
      (node (ref "IC17") (pin "6") (pinfunction "-IN_6") (pintype "input"))
      (node (ref "IC17") (pin "7") (pinfunction "OUT_7") (pintype "output"))
      (node (ref "R76") (pin "1") (pinfunction "1_1") (pintype "passive"))
      (node (ref "R77") (pin "1") (pinfunction "1_1") (pintype "passive"))
      (node (ref "R84") (pin "1") (pinfunction "1_1") (pintype "passive"))
    )
    (net (code "151") (name "unconnected-(CON1-Pad1)") (class "Default")
      (node (ref "CON1") (pin "1") (pinfunction "1_1") (pintype "passive"))
    )
    (net (code "152") (name "unconnected-(CON1-Pad4)") (class "Default")
      (node (ref "CON1") (pin "4") (pinfunction "4_4") (pintype "passive"))
    )
    (net (code "153") (name "unconnected-(CON1-Pad6)") (class "Default")
      (node (ref "CON1") (pin "6") (pinfunction "6_6") (pintype "passive"))
    )
    (net (code "154") (name "unconnected-(CON1-Pad7)") (class "Default")
      (node (ref "CON1") (pin "7") (pinfunction "7_7") (pintype "passive"))
    )
    (net (code "155") (name "unconnected-(CON1-Pad8)") (class "Default")
      (node (ref "CON1") (pin "8") (pinfunction "8_8") (pintype "passive"))
    )
    (net (code "156") (name "unconnected-(CON1-Pad9)") (class "Default")
      (node (ref "CON1") (pin "9") (pinfunction "9_9") (pintype "passive"))
    )
    (net (code "157") (name "unconnected-(IC2-NC-Pad3)") (class "Default")
      (node (ref "IC2") (pin "3") (pinfunction "NC_3") (pintype "passive"))
    )
    (net (code "158") (name "unconnected-(IC2-TP-Pad1)") (class "Default")
      (node (ref "IC2") (pin "1") (pinfunction "TP_1") (pintype "passive"))
    )
    (net (code "159") (name "unconnected-(IC2-TP-Pad5)") (class "Default")
      (node (ref "IC2") (pin "5") (pinfunction "TP_5") (pintype "passive"))
    )
    (net (code "160") (name "unconnected-(IC2-TRIM-Pad8)") (class "Default")
      (node (ref "IC2") (pin "8") (pinfunction "TRIM_8") (pintype "passive"))
    )
    (net (code "161") (name "unconnected-(IC2-VOUT-Pad7)") (class "Default")
      (node (ref "IC2") (pin "7") (pinfunction "VOUT_7") (pintype "passive"))
    )
    (net (code "162") (name "unconnected-(IC7-NC-Pad1)") (class "Default")
      (node (ref "IC7") (pin "1") (pinfunction "NC_1") (pintype "no_connect"))
    )
    (net (code "163") (name "unconnected-(IC7-NC-Pad8)") (class "Default")
      (node (ref "IC7") (pin "8") (pinfunction "NC_8") (pintype "no_connect"))
    )
    (net (code "164") (name "unconnected-(IC10-NC-Pad1)") (class "Default")
      (node (ref "IC10") (pin "1") (pinfunction "NC_1") (pintype "no_connect"))
    )
    (net (code "165") (name "unconnected-(IC10-NC-Pad8)") (class "Default")
      (node (ref "IC10") (pin "8") (pinfunction "NC_8") (pintype "no_connect"))
    )
    (net (code "166") (name "unconnected-(IC11-NC-Pad1)") (class "Default")
      (node (ref "IC11") (pin "1") (pinfunction "NC_1") (pintype "no_connect"))
    )
    (net (code "167") (name "unconnected-(IC11-NC-Pad8)") (class "Default")
      (node (ref "IC11") (pin "8") (pinfunction "NC_8") (pintype "no_connect"))
    )
    (net (code "168") (name "unconnected-(IC19-AIO-Pad27)") (class "Default")
      (node (ref "IC19") (pin "27") (pinfunction "AIO_27") (pintype "passive"))
    )
    (net (code "169") (name "unconnected-(IC19-MISO-Pad23)") (class "Default")
      (node (ref "IC19") (pin "23") (pinfunction "MISO_23") (pintype "passive"))
    )
    (net (code "170") (name "unconnected-(IC19-MOSI-Pad24)") (class "Default")
      (node (ref "IC19") (pin "24") (pinfunction "MOSI_24") (pintype "passive"))
    )
    (net (code "171") (name "unconnected-(IC19-NCSB-Pad21)") (class "Default")
      (node (ref "IC19") (pin "21") (pinfunction "NCSB_21") (pintype "passive"))
    )
    (net (code "172") (name "unconnected-(IC19-PCMC-Pad12)") (class "Default")
      (node (ref "IC19") (pin "12") (pinfunction "PCMC_12") (pintype "passive"))
    )
    (net (code "173") (name "unconnected-(IC19-PCMI-Pad11)") (class "Default")
      (node (ref "IC19") (pin "11") (pinfunction "PCMI_11") (pintype "passive"))
    )
    (net (code "174") (name "unconnected-(IC19-PCMO-Pad7)") (class "Default")
      (node (ref "IC19") (pin "7") (pinfunction "PCMO_7") (pintype "passive"))
    )
    (net (code "175") (name "unconnected-(IC19-PCMS-Pad13)") (class "Default")
      (node (ref "IC19") (pin "13") (pinfunction "PCMS_13") (pintype "passive"))
    )
    (net (code "176") (name "unconnected-(IC19-PIO2-Pad3)") (class "Default")
      (node (ref "IC19") (pin "3") (pinfunction "PIO2_3") (pintype "passive"))
    )
    (net (code "177") (name "unconnected-(IC19-PIO3-Pad4)") (class "Default")
      (node (ref "IC19") (pin "4") (pinfunction "PIO3_4") (pintype "passive"))
    )
    (net (code "178") (name "unconnected-(IC19-PIO4-Pad20)") (class "Default")
      (node (ref "IC19") (pin "20") (pinfunction "PIO4_20") (pintype "passive"))
    )
    (net (code "179") (name "unconnected-(IC19-PIO5-Pad25)") (class "Default")
      (node (ref "IC19") (pin "25") (pinfunction "PIO5_25") (pintype "passive"))
    )
    (net (code "180") (name "unconnected-(IC19-PIO6-Pad18)") (class "Default")
      (node (ref "IC19") (pin "18") (pinfunction "PIO6_18") (pintype "passive"))
    )
    (net (code "181") (name "unconnected-(IC19-PIO7-Pad19)") (class "Default")
      (node (ref "IC19") (pin "19") (pinfunction "PIO7_19") (pintype "passive"))
    )
    (net (code "182") (name "unconnected-(IC19-SCLK-Pad22)") (class "Default")
      (node (ref "IC19") (pin "22") (pinfunction "SCLK_22") (pintype "passive"))
    )
    (net (code "183") (name "unconnected-(IC19-USB_D+-Pad8)") (class "Default")
      (node (ref "IC19") (pin "8") (pinfunction "USB_D+_8") (pintype "passive"))
    )
    (net (code "184") (name "unconnected-(IC19-USB_D--Pad9)") (class "Default")
      (node (ref "IC19") (pin "9") (pinfunction "USB_D-_9") (pintype "passive"))
    )
    (net (code "185") (name "unconnected-(IC20-AIO-Pad27)") (class "Default")
      (node (ref "IC20") (pin "27") (pinfunction "AIO_27") (pintype "passive"))
    )
    (net (code "186") (name "unconnected-(IC20-MISO-Pad23)") (class "Default")
      (node (ref "IC20") (pin "23") (pinfunction "MISO_23") (pintype "passive"))
    )
    (net (code "187") (name "unconnected-(IC20-MOSI-Pad24)") (class "Default")
      (node (ref "IC20") (pin "24") (pinfunction "MOSI_24") (pintype "passive"))
    )
    (net (code "188") (name "unconnected-(IC20-NCSB-Pad21)") (class "Default")
      (node (ref "IC20") (pin "21") (pinfunction "NCSB_21") (pintype "passive"))
    )
    (net (code "189") (name "unconnected-(IC20-PCMC-Pad12)") (class "Default")
      (node (ref "IC20") (pin "12") (pinfunction "PCMC_12") (pintype "passive"))
    )
    (net (code "190") (name "unconnected-(IC20-PCMI-Pad11)") (class "Default")
      (node (ref "IC20") (pin "11") (pinfunction "PCMI_11") (pintype "passive"))
    )
    (net (code "191") (name "unconnected-(IC20-PCMO-Pad7)") (class "Default")
      (node (ref "IC20") (pin "7") (pinfunction "PCMO_7") (pintype "passive"))
    )
    (net (code "192") (name "unconnected-(IC20-PCMS-Pad13)") (class "Default")
      (node (ref "IC20") (pin "13") (pinfunction "PCMS_13") (pintype "passive"))
    )
    (net (code "193") (name "unconnected-(IC20-PIO2-Pad3)") (class "Default")
      (node (ref "IC20") (pin "3") (pinfunction "PIO2_3") (pintype "passive"))
    )
    (net (code "194") (name "unconnected-(IC20-PIO3-Pad4)") (class "Default")
      (node (ref "IC20") (pin "4") (pinfunction "PIO3_4") (pintype "passive"))
    )
    (net (code "195") (name "unconnected-(IC20-PIO4-Pad20)") (class "Default")
      (node (ref "IC20") (pin "20") (pinfunction "PIO4_20") (pintype "passive"))
    )
    (net (code "196") (name "unconnected-(IC20-PIO5-Pad25)") (class "Default")
      (node (ref "IC20") (pin "25") (pinfunction "PIO5_25") (pintype "passive"))
    )
    (net (code "197") (name "unconnected-(IC20-PIO6-Pad18)") (class "Default")
      (node (ref "IC20") (pin "18") (pinfunction "PIO6_18") (pintype "passive"))
    )
    (net (code "198") (name "unconnected-(IC20-PIO7-Pad19)") (class "Default")
      (node (ref "IC20") (pin "19") (pinfunction "PIO7_19") (pintype "passive"))
    )
    (net (code "199") (name "unconnected-(IC20-SCLK-Pad22)") (class "Default")
      (node (ref "IC20") (pin "22") (pinfunction "SCLK_22") (pintype "passive"))
    )
    (net (code "200") (name "unconnected-(IC20-USB_D+-Pad8)") (class "Default")
      (node (ref "IC20") (pin "8") (pinfunction "USB_D+_8") (pintype "passive"))
    )
    (net (code "201") (name "unconnected-(IC20-USB_D--Pad9)") (class "Default")
      (node (ref "IC20") (pin "9") (pinfunction "USB_D-_9") (pintype "passive"))
    )
    (net (code "202") (name "unconnected-(IC21A-R2OUT-Pad9)") (class "Default")
      (node (ref "IC21") (pin "9") (pinfunction "R2OUT_9") (pintype "output"))
    )
    (net (code "203") (name "unconnected-(IC21A-T2OUT-Pad7)") (class "Default")
      (node (ref "IC21") (pin "7") (pinfunction "T2OUT_7") (pintype "output"))
    )
    (net (code "204") (name "unconnected-(J22D-S-Pad4)") (class "Default")
      (node (ref "J22") (pin "4") (pinfunction "S_4") (pintype "passive"))
    )
    (net (code "205") (name "unconnected-(J23D-S-Pad4)") (class "Default")
      (node (ref "J23") (pin "4") (pinfunction "S_4") (pintype "passive"))
    )
    (net (code "206") (name "unconnected-(J24D-S-Pad4)") (class "Default")
      (node (ref "J24") (pin "4") (pinfunction "S_4") (pintype "passive"))
    )
    (net (code "207") (name "unconnected-(K1-PadO)") (class "Default")
      (node (ref "K1") (pin "O") (pinfunction "O_O") (pintype "passive"))
    )
  )
)
